# AI_Camera_V1_0.net
KiCad netlist of a schematic drawn in EAGLE
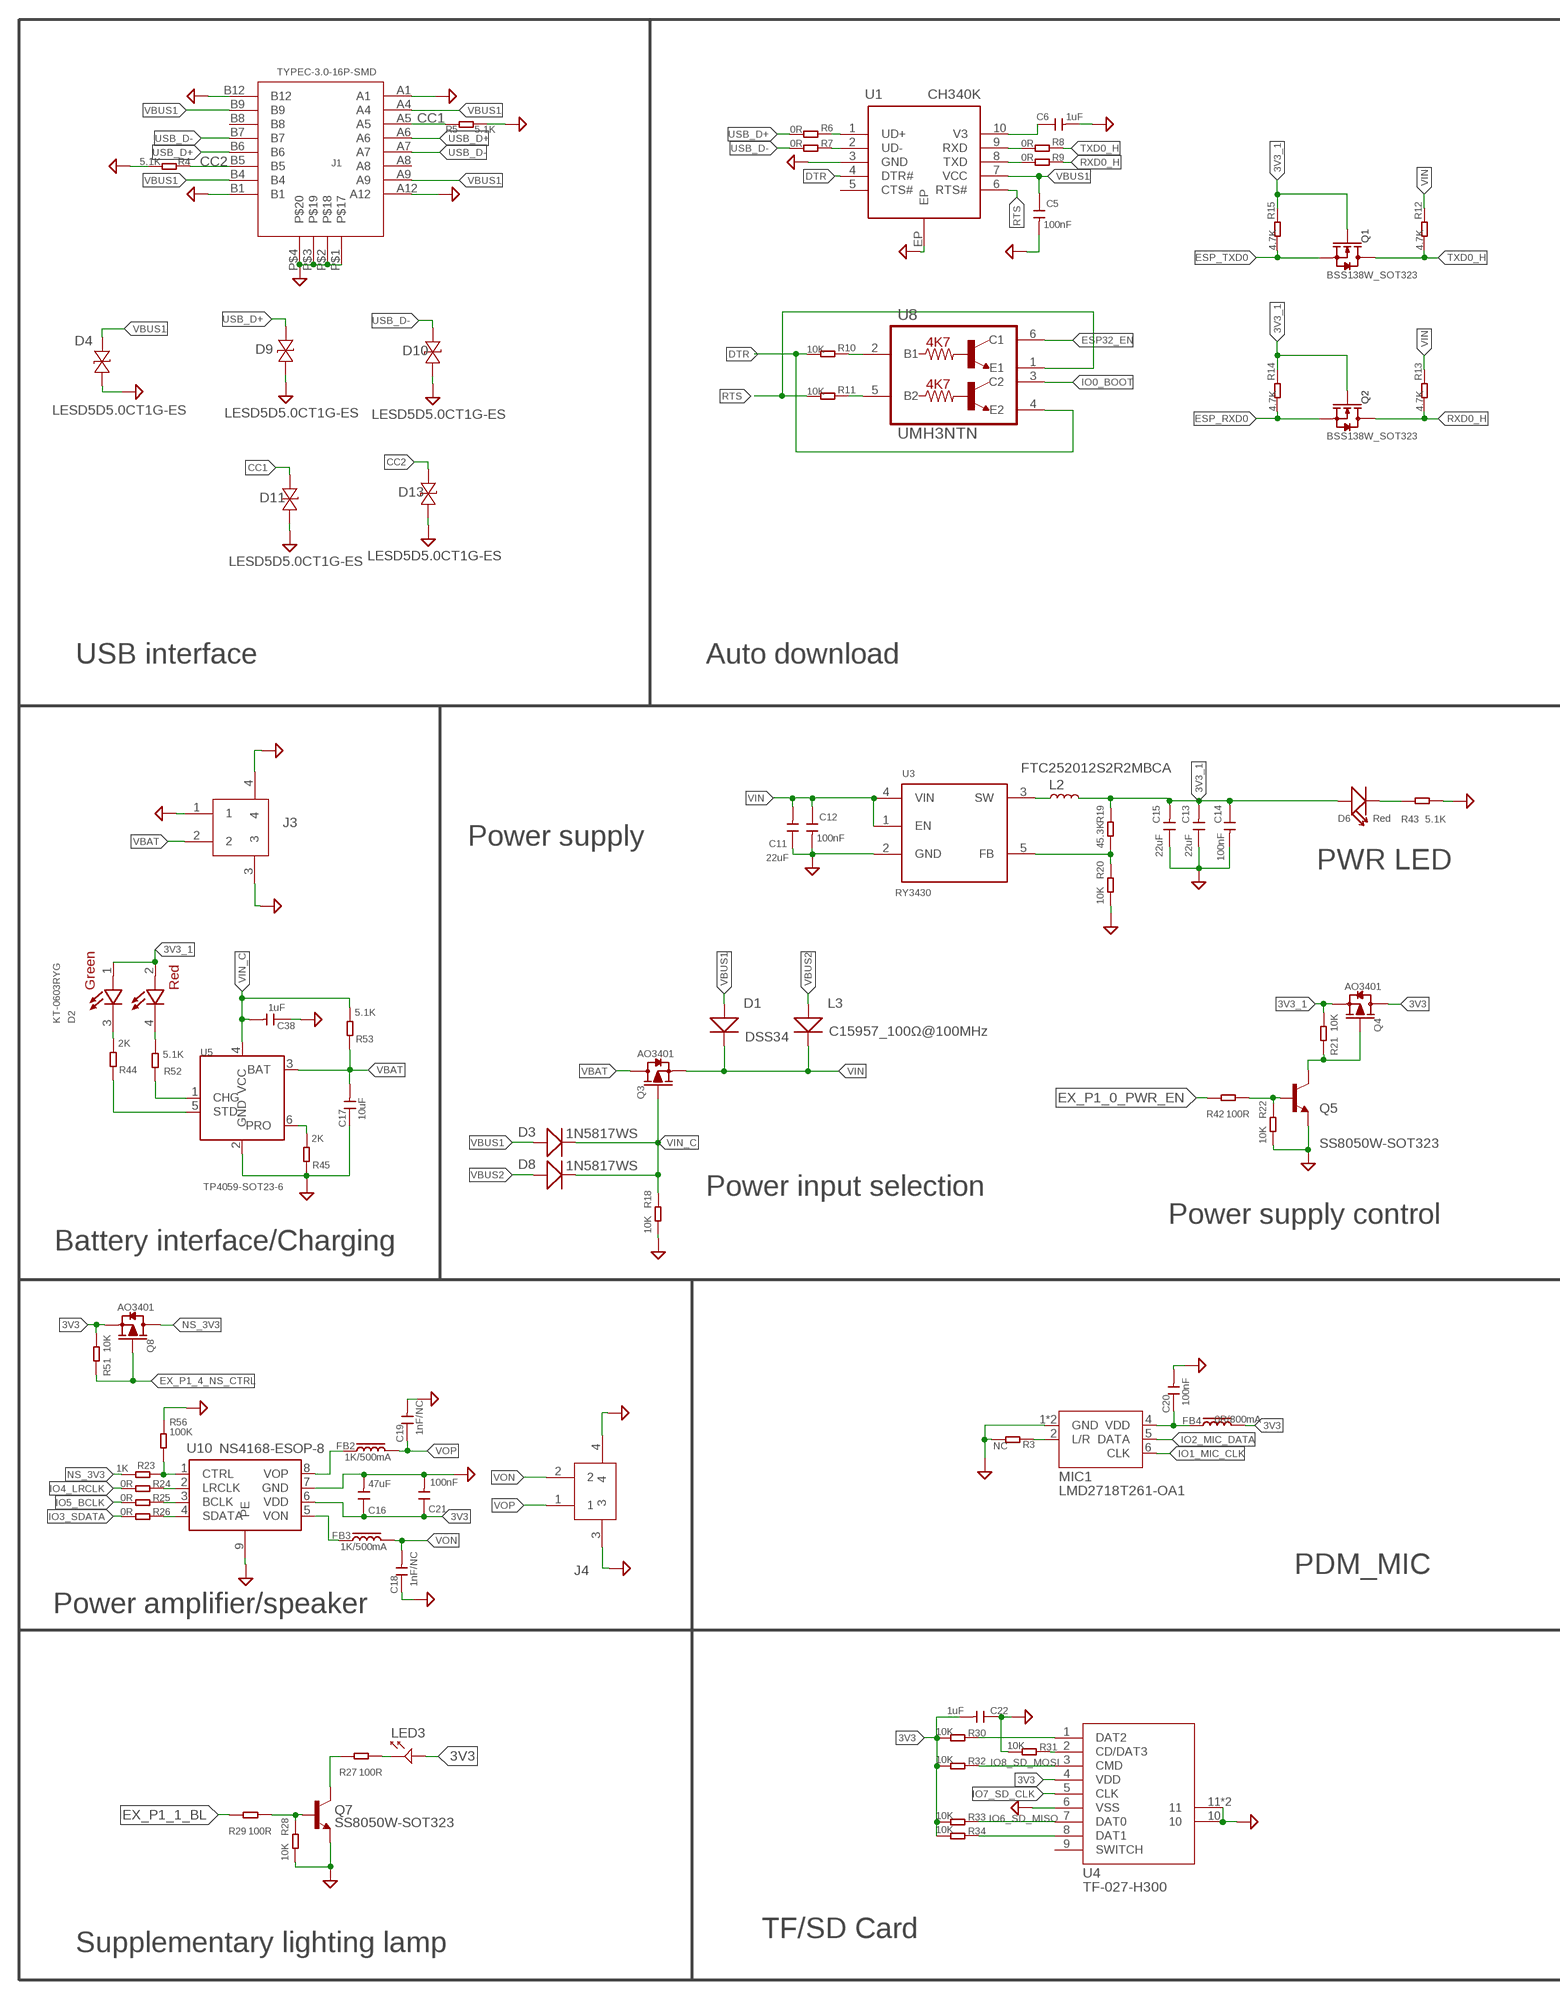
[diagram p0: schematic, sheet 1, part 1 of 2]
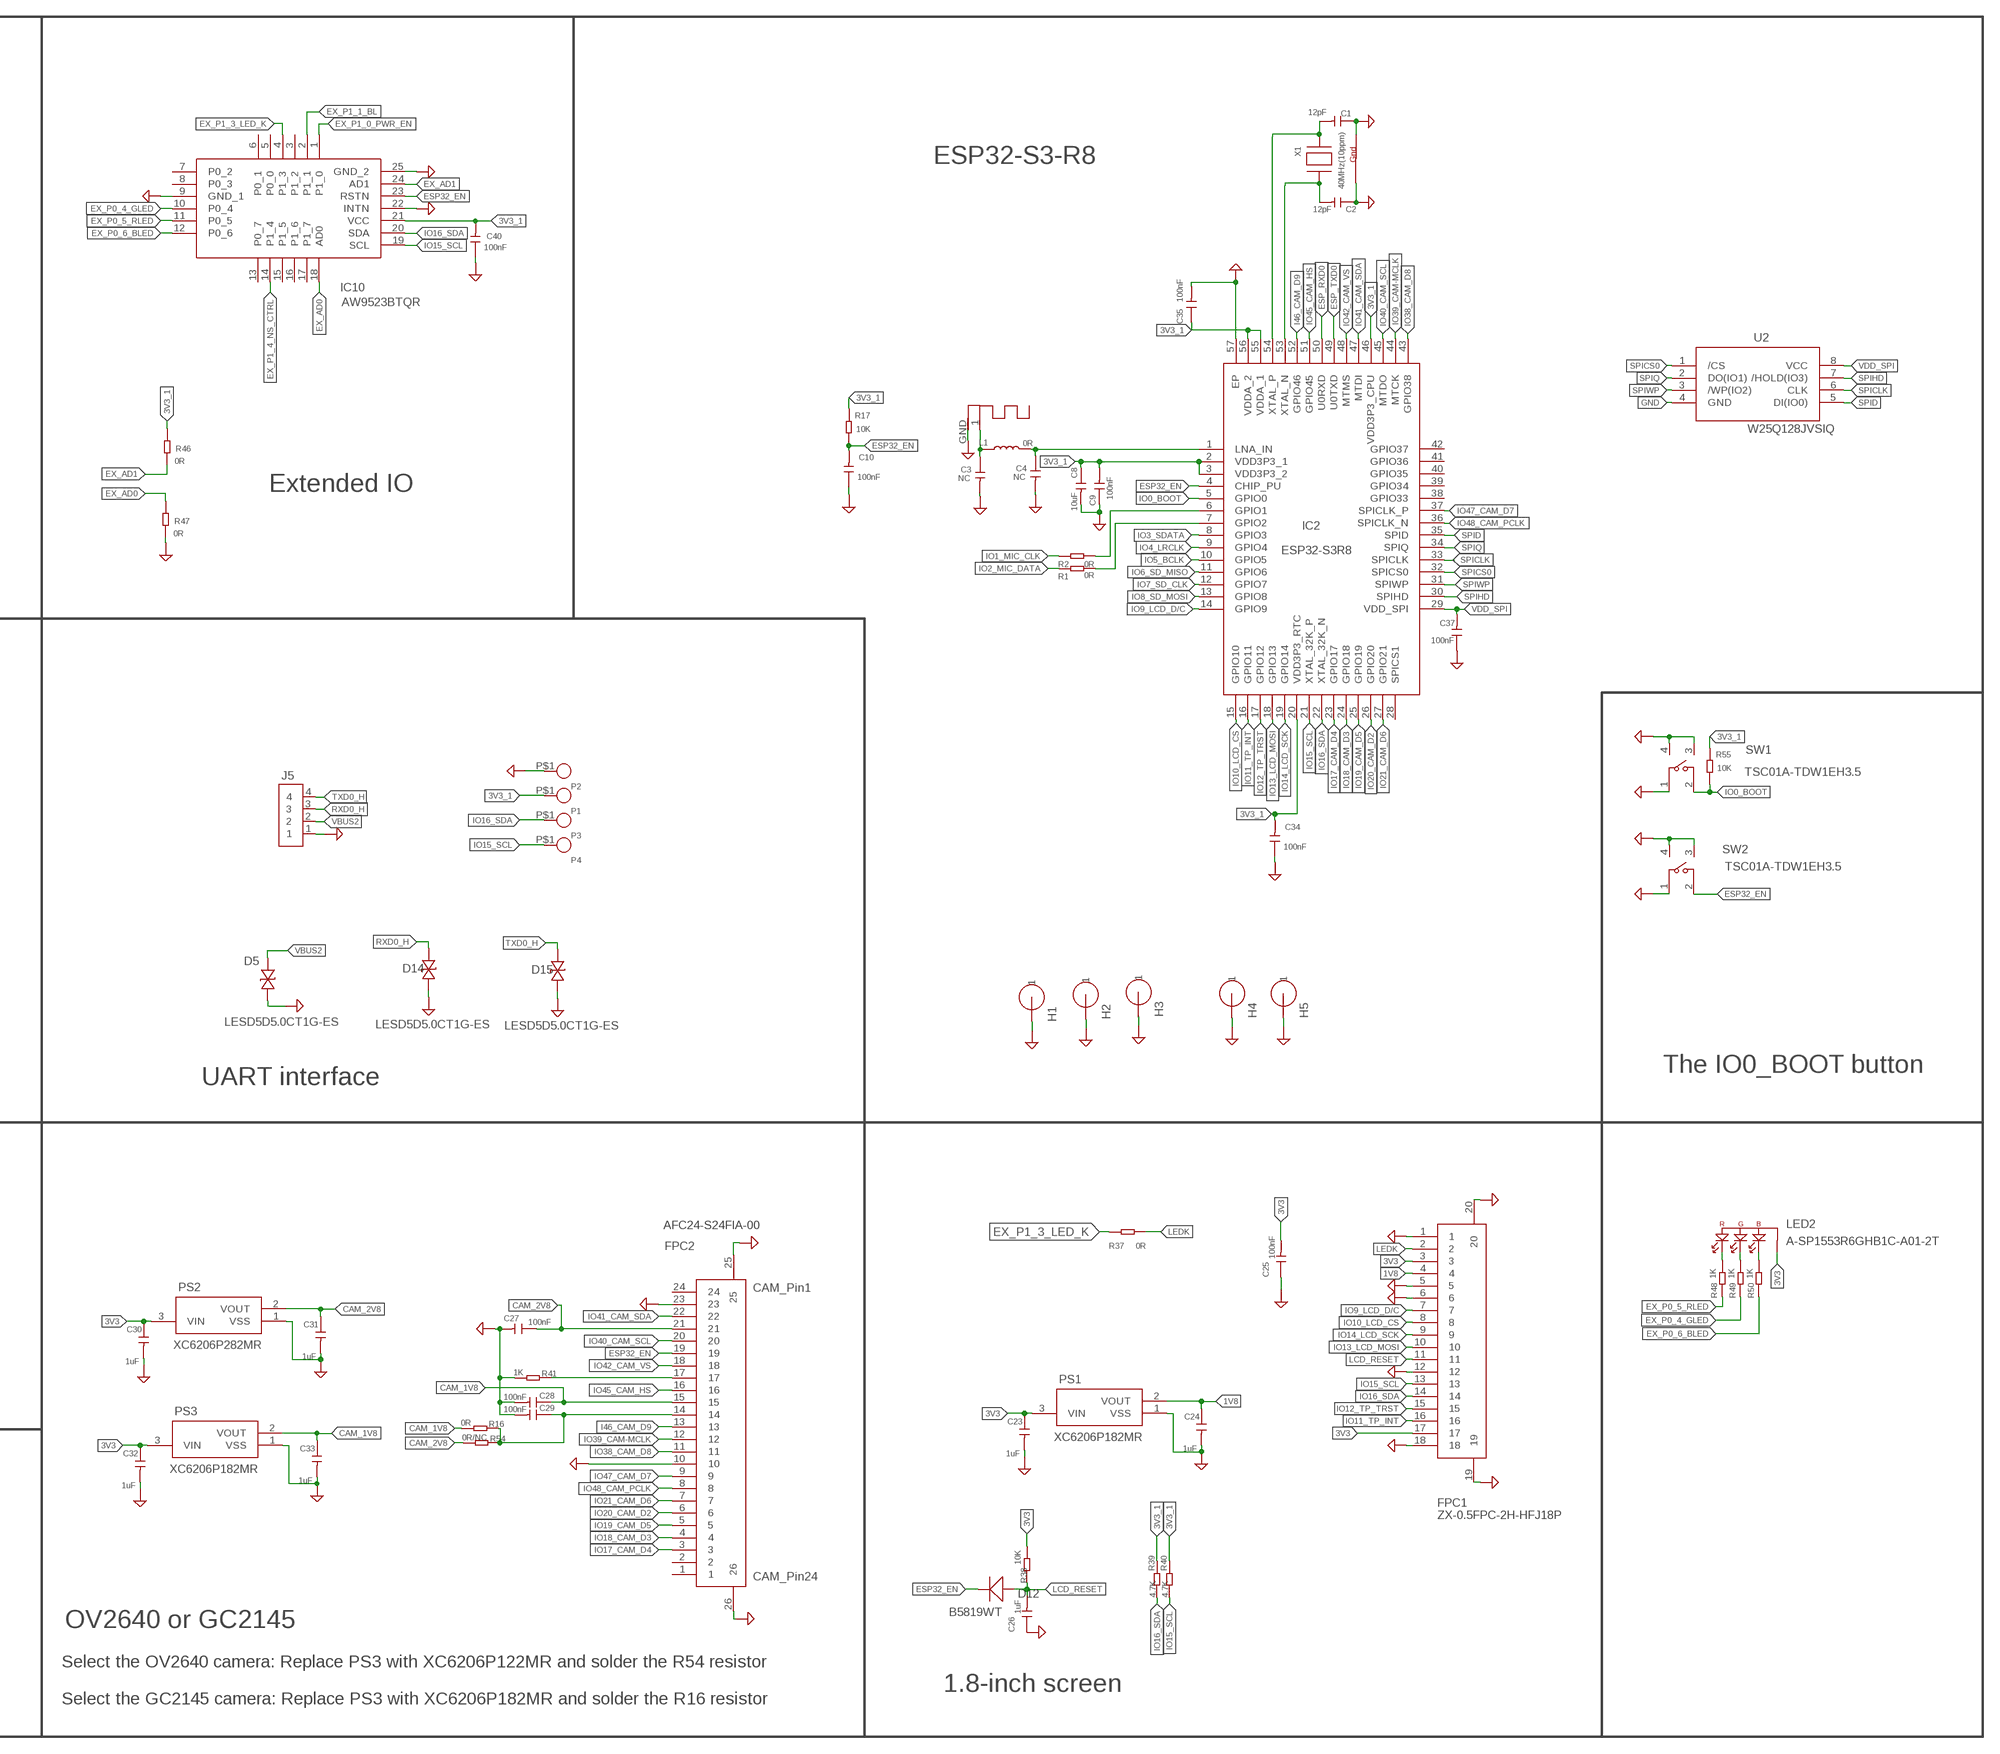
[diagram p1: schematic, sheet 1, part 2 of 2]

(export (version "E")
  (design (tool "Eeschema 10.0.6"))
  (components
    (comp (ref "ANT1")
      (value "ADAFRUIT_ANTENNA")
      (footprint "eagle-import:ADAFRUIT_RN-ANT")
      (libsource (lib "eagle-import") (part "ADAFRUIT_ANTENNA"))
    )
    (comp (ref "C1")
      (value "12pF")
      (footprint "eagle-import:C0402")
      (libsource (lib "eagle-import") (part "CAPC0402-1"))
    )
    (comp (ref "C2")
      (value "12pF")
      (footprint "eagle-import:C0402")
      (libsource (lib "eagle-import") (part "CAPC0402-1"))
    )
    (comp (ref "C3")
      (value "NC")
      (footprint "eagle-import:C0402")
      (libsource (lib "eagle-import") (part "CAPC0402-1"))
    )
    (comp (ref "C4")
      (value "NC")
      (footprint "eagle-import:C0402")
      (libsource (lib "eagle-import") (part "CAPC0402-1"))
    )
    (comp (ref "C5")
      (value "100nF")
      (footprint "eagle-import:C0402")
      (libsource (lib "eagle-import") (part "CAPC0402-1"))
    )
    (comp (ref "C6")
      (value "1uF")
      (footprint "eagle-import:C0402")
      (libsource (lib "eagle-import") (part "CAPC0402-1"))
    )
    (comp (ref "C8")
      (value "10uF")
      (footprint "eagle-import:C0402")
      (libsource (lib "eagle-import") (part "CAPC0402-1"))
    )
    (comp (ref "C9")
      (value "100nF")
      (footprint "eagle-import:C0402")
      (libsource (lib "eagle-import") (part "CAPC0402-1"))
    )
    (comp (ref "C10")
      (value "100nF")
      (footprint "eagle-import:C0402")
      (libsource (lib "eagle-import") (part "CAPC0402-1"))
    )
    (comp (ref "C11")
      (value "22uF")
      (footprint "eagle-import:C0603")
      (libsource (lib "eagle-import") (part "CAP"))
    )
    (comp (ref "C12")
      (value "100nF")
      (footprint "eagle-import:C0402")
      (libsource (lib "eagle-import") (part "CAPC0402-1"))
    )
    (comp (ref "C13")
      (value "22uF")
      (footprint "eagle-import:C0603")
      (libsource (lib "eagle-import") (part "CAP"))
    )
    (comp (ref "C14")
      (value "100nF")
      (footprint "eagle-import:C0402")
      (libsource (lib "eagle-import") (part "CAPC0402-1"))
    )
    (comp (ref "C15")
      (value "22uF")
      (footprint "eagle-import:C0603")
      (libsource (lib "eagle-import") (part "CAP"))
    )
    (comp (ref "C16")
      (value "47uF")
      (footprint "eagle-import:C0805")
      (libsource (lib "eagle-import") (part "CAPC0805"))
    )
    (comp (ref "C17")
      (value "10uF")
      (footprint "eagle-import:C0402")
      (libsource (lib "eagle-import") (part "CAPC0402-1"))
    )
    (comp (ref "C18")
      (value "1nF/NC")
      (footprint "eagle-import:C0402")
      (libsource (lib "eagle-import") (part "CAPC0402-1"))
    )
    (comp (ref "C19")
      (value "1nF/NC")
      (footprint "eagle-import:C0402")
      (libsource (lib "eagle-import") (part "CAPC0402-1"))
    )
    (comp (ref "C20")
      (value "100nF")
      (footprint "eagle-import:C0402")
      (libsource (lib "eagle-import") (part "CAPC0402-1"))
    )
    (comp (ref "C21")
      (value "100nF")
      (footprint "eagle-import:C0402")
      (libsource (lib "eagle-import") (part "CAPC0402-1"))
    )
    (comp (ref "C22")
      (value "1uF")
      (footprint "eagle-import:C0402")
      (libsource (lib "eagle-import") (part "CAPC0402-1"))
    )
    (comp (ref "C23")
      (value "1uF")
      (footprint "eagle-import:C0402")
      (libsource (lib "eagle-import") (part "CAPC0402-1"))
    )
    (comp (ref "C24")
      (value "1uF")
      (footprint "eagle-import:C0402")
      (libsource (lib "eagle-import") (part "CAPC0402-1"))
    )
    (comp (ref "C25")
      (value "100nF")
      (footprint "eagle-import:C0402")
      (libsource (lib "eagle-import") (part "CAPC0402-1"))
    )
    (comp (ref "C26")
      (value "1uF")
      (footprint "eagle-import:C0402")
      (libsource (lib "eagle-import") (part "CAPC0402-1"))
    )
    (comp (ref "C27")
      (value "100nF")
      (footprint "eagle-import:C0402")
      (libsource (lib "eagle-import") (part "CAPC0402-1"))
    )
    (comp (ref "C28")
      (value "100nF")
      (footprint "eagle-import:C0402")
      (libsource (lib "eagle-import") (part "CAPC0402-1"))
    )
    (comp (ref "C29")
      (value "100nF")
      (footprint "eagle-import:C0402")
      (libsource (lib "eagle-import") (part "CAPC0402-1"))
    )
    (comp (ref "C30")
      (value "1uF")
      (footprint "eagle-import:C0402")
      (libsource (lib "eagle-import") (part "CAPC0402-1"))
    )
    (comp (ref "C31")
      (value "1uF")
      (footprint "eagle-import:C0402")
      (libsource (lib "eagle-import") (part "CAPC0402-1"))
    )
    (comp (ref "C32")
      (value "1uF")
      (footprint "eagle-import:C0402")
      (libsource (lib "eagle-import") (part "CAPC0402-1"))
    )
    (comp (ref "C33")
      (value "1uF")
      (footprint "eagle-import:C0402")
      (libsource (lib "eagle-import") (part "CAPC0402-1"))
    )
    (comp (ref "C34")
      (value "100nF")
      (footprint "eagle-import:C0402")
      (libsource (lib "eagle-import") (part "CAPC0402-1"))
    )
    (comp (ref "C35")
      (value "100nF")
      (footprint "eagle-import:C0402")
      (libsource (lib "eagle-import") (part "CAPC0402-1"))
    )
    (comp (ref "C37")
      (value "100nF")
      (footprint "eagle-import:C0402")
      (libsource (lib "eagle-import") (part "CAPC0402-1"))
    )
    (comp (ref "C38")
      (value "1uF")
      (footprint "eagle-import:C0402")
      (libsource (lib "eagle-import") (part "CAPC0402-1"))
    )
    (comp (ref "C40")
      (value "100nF")
      (footprint "eagle-import:C0402")
      (libsource (lib "eagle-import") (part "CAPC0402-1"))
    )
    (comp (ref "D1")
      (value "DSS34")
      (footprint "eagle-import:D_SOD123FL")
      (libsource (lib "eagle-import") (part "DIODE"))
    )
    (comp (ref "D2")
      (value "KT-0603RYG")
      (footprint "eagle-import:LED_KT-0603RYG")
      (libsource (lib "eagle-import") (part "KT-0603RYG"))
    )
    (comp (ref "D3")
      (value "1N5817WS")
      (footprint "eagle-import:D_SOD323")
      (libsource (lib "eagle-import") (part "DIODE0805"))
    )
    (comp (ref "D4")
      (value "LESD5D5.0CT1G-ES")
      (footprint "eagle-import:SOD-523_L1.2-W0.8-LS1.6-BI")
      (libsource (lib "eagle-import") (part "LESD5D5.0CT1G-ES"))
    )
    (comp (ref "D5")
      (value "LESD5D5.0CT1G-ES")
      (footprint "eagle-import:SOD-523_L1.2-W0.8-LS1.6-BI")
      (libsource (lib "eagle-import") (part "LESD5D5.0CT1G-ES"))
    )
    (comp (ref "D6")
      (value "Red")
      (footprint "eagle-import:LED0603")
      (libsource (lib "eagle-import") (part "LED-SMT0603"))
    )
    (comp (ref "D8")
      (value "1N5817WS")
      (footprint "eagle-import:D_SOD323")
      (libsource (lib "eagle-import") (part "DIODE0805"))
    )
    (comp (ref "D9")
      (value "LESD5D5.0CT1G-ES")
      (footprint "eagle-import:SOD-523_L1.2-W0.8-LS1.6-BI")
      (libsource (lib "eagle-import") (part "LESD5D5.0CT1G-ES"))
    )
    (comp (ref "D10")
      (value "LESD5D5.0CT1G-ES")
      (footprint "eagle-import:SOD-523_L1.2-W0.8-LS1.6-BI")
      (libsource (lib "eagle-import") (part "LESD5D5.0CT1G-ES"))
    )
    (comp (ref "D11")
      (value "LESD5D5.0CT1G-ES")
      (footprint "eagle-import:SOD-523_L1.2-W0.8-LS1.6-BI")
      (libsource (lib "eagle-import") (part "LESD5D5.0CT1G-ES"))
    )
    (comp (ref "D12")
      (value "B5819WT")
      (footprint "eagle-import:D_SOD523")
      (libsource (lib "eagle-import") (part "DIODE0603"))
    )
    (comp (ref "D13")
      (value "LESD5D5.0CT1G-ES")
      (footprint "eagle-import:SOD-523_L1.2-W0.8-LS1.6-BI")
      (libsource (lib "eagle-import") (part "LESD5D5.0CT1G-ES"))
    )
    (comp (ref "D14")
      (value "LESD5D5.0CT1G-ES")
      (footprint "eagle-import:SOD-523_L1.2-W0.8-LS1.6-BI")
      (libsource (lib "eagle-import") (part "LESD5D5.0CT1G-ES"))
    )
    (comp (ref "D15")
      (value "LESD5D5.0CT1G-ES")
      (footprint "eagle-import:SOD-523_L1.2-W0.8-LS1.6-BI")
      (libsource (lib "eagle-import") (part "LESD5D5.0CT1G-ES"))
    )
    (comp (ref "FB2")
      (value "1K/500mA")
      (footprint "eagle-import:L0603")
      (libsource (lib "eagle-import") (part "FBL0603"))
    )
    (comp (ref "FB3")
      (value "1K/500mA")
      (footprint "eagle-import:L0603")
      (libsource (lib "eagle-import") (part "FBL0603"))
    )
    (comp (ref "FB4")
      (value "0R/800mA")
      (footprint "eagle-import:L0603")
      (libsource (lib "eagle-import") (part "FBL0603"))
    )
    (comp (ref "FPC1")
      (value "ZX-0.5FPC-2H-HFJ18P")
      (footprint "eagle-import:FPC-SMD_18P-P0.50_ZX-0.5FPC-2H-HFJ18P")
      (libsource (lib "eagle-import") (part "ZX-0.5FPC-2H-HFJ18P"))
    )
    (comp (ref "FPC2")
      (value "AFC24-S24FIA-00")
      (footprint "eagle-import:FPC-SMD_P0.50-24P_QCHF-SM-H2.0")
      (libsource (lib "eagle-import") (part "AFC24-S24FIA-00"))
    )
    (comp (ref "H1")
      (value "HOLE")
      (footprint "eagle-import:HOLE_M2")
      (libsource (lib "eagle-import") (part "HOLE"))
    )
    (comp (ref "H2")
      (value "HOLE")
      (footprint "eagle-import:HOLE_M2")
      (libsource (lib "eagle-import") (part "HOLE"))
    )
    (comp (ref "H3")
      (value "HOLE")
      (footprint "eagle-import:HOLE_M2")
      (libsource (lib "eagle-import") (part "HOLE"))
    )
    (comp (ref "H4")
      (value "HOLE1")
      (footprint "eagle-import:LONGSTRIPHOLE")
      (libsource (lib "eagle-import") (part "HOLE1"))
    )
    (comp (ref "H5")
      (value "HOLE1")
      (footprint "eagle-import:LONGSTRIPHOLE")
      (libsource (lib "eagle-import") (part "HOLE1"))
    )
    (comp (ref "IC2")
      (value "ESP32-S3R8")
      (footprint "eagle-import:QFN40P700X700X90-57N")
      (fields (field (name "MOUSER_PART_NUMBER") "356-ESP32-S3R8"))
      (libsource (lib "eagle-import") (part "ESP32-S3R8"))
    )
    (comp (ref "IC10")
      (value "AW9523BTQR")
      (footprint "eagle-import:QFN50P400X400X80-25N")
      (libsource (lib "eagle-import") (part "AW9523BTQR"))
    )
    (comp (ref "J1")
      (value "TYPEC-3.0-16P-SMD")
      (footprint "eagle-import:USB-3.0TYPEC-SMD")
      (libsource (lib "eagle-import") (part "TYPEC-3.0-16P-SMD"))
    )
    (comp (ref "J3")
      (value "ZX-SH1.0-2PLT1")
      (footprint "eagle-import:CONN-SMD_2P-P1.00_XUNPU_WAFER-SH1.0-2PWB")
      (libsource (lib "eagle-import") (part "ZX-SH1.0-2PLT1"))
    )
    (comp (ref "J4")
      (value "HC-1.25-2PWT")
      (footprint "eagle-import:CONN-SMD_2P-P1.25-HC-1.25-2PWT")
      (libsource (lib "eagle-import") (part "HC-1.25-2PWT"))
    )
    (comp (ref "J5")
      (value "HC-HY-4A-M")
      (footprint "eagle-import:CONN-TH_4P-P2.00_HCTL_HC-HY-4A")
      (libsource (lib "eagle-import") (part "HC-HY-4A-M"))
    )
    (comp (ref "L1")
      (value "0R")
      (footprint "eagle-import:L0402")
      (libsource (lib "eagle-import") (part "L0402"))
    )
    (comp (ref "L2")
      (value "FTC252012S2R2MBCA")
      (footprint "eagle-import:IND-SMD_L2.5-W2.0_MHCHL2520")
      (libsource (lib "eagle-import") (part "FTC252012S2R2MBCA"))
    )
    (comp (ref "L3")
      (value "C15957_100Ω@100MHz")
      (footprint "eagle-import:D_SOD123FL")
      (libsource (lib "eagle-import") (part "DIODE"))
    )
    (comp (ref "LED2")
      (value "A-SP1553R6GHB1C-A01-2T")
      (footprint "eagle-import:LED-SMD_4P-L3.2-W2.7-BL_A-SP1553R6GHB1C-A01-2T")
      (libsource (lib "eagle-import") (part "A-SP1553R6GHB1C-A01-2T"))
    )
    (comp (ref "LED3")
      (value "3014_LED")
      (footprint "eagle-import:LED_3014_SMT")
      (libsource (lib "eagle-import") (part "3014_LED"))
    )
    (comp (ref "MIC1")
      (value "LMD2718T261-OA1")
      (footprint "eagle-import:MIC-SMD_6P-L2.8-W1.9-P0.98-TL")
      (libsource (lib "eagle-import") (part "LMD2718T261-OA1"))
    )
    (comp (ref "P1")
      (value "TEST_PADPAD-1.5MM")
      (footprint "eagle-import:TEST_PAD-1.5MM")
      (libsource (lib "eagle-import") (part "TEST_PADPAD-1.5MM"))
    )
    (comp (ref "P2")
      (value "TEST_PADPAD-1.5MM")
      (footprint "eagle-import:TEST_PAD-1.5MM")
      (libsource (lib "eagle-import") (part "TEST_PADPAD-1.5MM"))
    )
    (comp (ref "P3")
      (value "TEST_PADPAD-1.5MM")
      (footprint "eagle-import:TEST_PAD-1.5MM")
      (libsource (lib "eagle-import") (part "TEST_PADPAD-1.5MM"))
    )
    (comp (ref "P4")
      (value "TEST_PADPAD-1.5MM")
      (footprint "eagle-import:TEST_PAD-1.5MM")
      (libsource (lib "eagle-import") (part "TEST_PADPAD-1.5MM"))
    )
    (comp (ref "PS1")
      (value "XC6206P182MR")
      (footprint "eagle-import:SOT95P280X130-3N")
      (libsource (lib "eagle-import") (part "XC6206P182MR"))
    )
    (comp (ref "PS2")
      (value "XC6206P282MR")
      (footprint "eagle-import:SOT95P280X130-3N")
      (fields (field (name "MANUFACTURER_PART_NUMBER") "XC6206P182MR"))
      (libsource (lib "eagle-import") (part "XC6206P182MR"))
    )
    (comp (ref "PS3")
      (value "XC6206P182MR")
      (footprint "eagle-import:SOT95P280X130-3N")
      (libsource (lib "eagle-import") (part "XC6206P182MR"))
    )
    (comp (ref "Q1")
      (value "BSS138W_SOT323")
      (footprint "eagle-import:MOS_SOT323")
      (libsource (lib "eagle-import") (part "MOSFET-NSI1304BDL"))
    )
    (comp (ref "Q2")
      (value "BSS138W_SOT323")
      (footprint "eagle-import:MOS_SOT323")
      (libsource (lib "eagle-import") (part "MOSFET-NSI1304BDL"))
    )
    (comp (ref "Q3")
      (value "AO3401")
      (footprint "eagle-import:PMOS_SOT23")
      (libsource (lib "eagle-import") (part "MOSFET-PSOT23"))
    )
    (comp (ref "Q4")
      (value "AO3401")
      (footprint "eagle-import:PMOS_SOT23")
      (libsource (lib "eagle-import") (part "MOSFET-PSOT23"))
    )
    (comp (ref "Q5")
      (value "SS8050W-SOT323")
      (footprint "eagle-import:MOS_SOT323")
      (libsource (lib "eagle-import") (part "TRANS_NPN"))
    )
    (comp (ref "Q7")
      (value "SS8050W-SOT323")
      (footprint "eagle-import:MOS_SOT323")
      (libsource (lib "eagle-import") (part "TRANS_NPN"))
    )
    (comp (ref "Q8")
      (value "AO3401")
      (footprint "eagle-import:PMOS_SOT23")
      (libsource (lib "eagle-import") (part "MOSFET-PSOT23"))
    )
    (comp (ref "R1")
      (value "0R")
      (footprint "eagle-import:R0402")
      (libsource (lib "eagle-import") (part "RES-0402"))
    )
    (comp (ref "R2")
      (value "0R")
      (footprint "eagle-import:R0402")
      (libsource (lib "eagle-import") (part "RES-0402"))
    )
    (comp (ref "R3")
      (value "NC")
      (footprint "eagle-import:R0402")
      (libsource (lib "eagle-import") (part "RES-0402"))
    )
    (comp (ref "R4")
      (value "5.1K")
      (footprint "eagle-import:R0402")
      (libsource (lib "eagle-import") (part "RES-0402"))
    )
    (comp (ref "R5")
      (value "5.1K")
      (footprint "eagle-import:R0402")
      (libsource (lib "eagle-import") (part "RES-0402"))
    )
    (comp (ref "R6")
      (value "0R")
      (footprint "eagle-import:R0402")
      (libsource (lib "eagle-import") (part "RES-0402"))
    )
    (comp (ref "R7")
      (value "0R")
      (footprint "eagle-import:R0402")
      (libsource (lib "eagle-import") (part "RES-0402"))
    )
    (comp (ref "R8")
      (value "0R")
      (footprint "eagle-import:R0402")
      (libsource (lib "eagle-import") (part "RES-0402"))
    )
    (comp (ref "R9")
      (value "0R")
      (footprint "eagle-import:R0402")
      (libsource (lib "eagle-import") (part "RES-0402"))
    )
    (comp (ref "R10")
      (value "10K")
      (footprint "eagle-import:R0402")
      (libsource (lib "eagle-import") (part "RES-0402"))
    )
    (comp (ref "R11")
      (value "10K")
      (footprint "eagle-import:R0402")
      (libsource (lib "eagle-import") (part "RES-0402"))
    )
    (comp (ref "R12")
      (value "4.7K")
      (footprint "eagle-import:R0402")
      (libsource (lib "eagle-import") (part "RES-0402"))
    )
    (comp (ref "R13")
      (value "4.7K")
      (footprint "eagle-import:R0402")
      (libsource (lib "eagle-import") (part "RES-0402"))
    )
    (comp (ref "R14")
      (value "4.7K")
      (footprint "eagle-import:R0402")
      (libsource (lib "eagle-import") (part "RES-0402"))
    )
    (comp (ref "R15")
      (value "4.7K")
      (footprint "eagle-import:R0402")
      (libsource (lib "eagle-import") (part "RES-0402"))
    )
    (comp (ref "R16")
      (value "0R")
      (footprint "eagle-import:R0402")
      (libsource (lib "eagle-import") (part "RES-0402"))
    )
    (comp (ref "R17")
      (value "10K")
      (footprint "eagle-import:R0402")
      (libsource (lib "eagle-import") (part "RES-0402"))
    )
    (comp (ref "R18")
      (value "10K")
      (footprint "eagle-import:R0402")
      (libsource (lib "eagle-import") (part "RES-0402"))
    )
    (comp (ref "R19")
      (value "45.3K")
      (footprint "eagle-import:R0402")
      (libsource (lib "eagle-import") (part "RES-0402"))
    )
    (comp (ref "R20")
      (value "10K")
      (footprint "eagle-import:R0402")
      (libsource (lib "eagle-import") (part "RES-0402"))
    )
    (comp (ref "R21")
      (value "10K")
      (footprint "eagle-import:R0402")
      (libsource (lib "eagle-import") (part "RES-0402"))
    )
    (comp (ref "R22")
      (value "10K")
      (footprint "eagle-import:R0402")
      (libsource (lib "eagle-import") (part "RES-0402"))
    )
    (comp (ref "R23")
      (value "1K")
      (footprint "eagle-import:R0402")
      (libsource (lib "eagle-import") (part "RES-0402"))
    )
    (comp (ref "R24")
      (value "0R")
      (footprint "eagle-import:R0402")
      (libsource (lib "eagle-import") (part "RES-0402"))
    )
    (comp (ref "R25")
      (value "0R")
      (footprint "eagle-import:R0402")
      (libsource (lib "eagle-import") (part "RES-0402"))
    )
    (comp (ref "R26")
      (value "0R")
      (footprint "eagle-import:R0402")
      (libsource (lib "eagle-import") (part "RES-0402"))
    )
    (comp (ref "R27")
      (value "100R")
      (footprint "eagle-import:R0402")
      (libsource (lib "eagle-import") (part "RES-0402"))
    )
    (comp (ref "R28")
      (value "10K")
      (footprint "eagle-import:R0402")
      (libsource (lib "eagle-import") (part "RES-0402"))
    )
    (comp (ref "R29")
      (value "100R")
      (footprint "eagle-import:R0402")
      (libsource (lib "eagle-import") (part "RES-0402"))
    )
    (comp (ref "R30")
      (value "10K")
      (footprint "eagle-import:R0402")
      (libsource (lib "eagle-import") (part "RES-0402"))
    )
    (comp (ref "R31")
      (value "10K")
      (footprint "eagle-import:R0402")
      (libsource (lib "eagle-import") (part "RES-0402"))
    )
    (comp (ref "R32")
      (value "10K")
      (footprint "eagle-import:R0402")
      (libsource (lib "eagle-import") (part "RES-0402"))
    )
    (comp (ref "R33")
      (value "10K")
      (footprint "eagle-import:R0402")
      (libsource (lib "eagle-import") (part "RES-0402"))
    )
    (comp (ref "R34")
      (value "10K")
      (footprint "eagle-import:R0402")
      (libsource (lib "eagle-import") (part "RES-0402"))
    )
    (comp (ref "R37")
      (value "0R")
      (footprint "eagle-import:R0402")
      (libsource (lib "eagle-import") (part "RES-0402"))
    )
    (comp (ref "R38")
      (value "10K")
      (footprint "eagle-import:R0402")
      (libsource (lib "eagle-import") (part "RES-0402"))
    )
    (comp (ref "R39")
      (value "4.7K")
      (footprint "eagle-import:R0402")
      (libsource (lib "eagle-import") (part "RES-0402"))
    )
    (comp (ref "R40")
      (value "4.7K")
      (footprint "eagle-import:R0402")
      (libsource (lib "eagle-import") (part "RES-0402"))
    )
    (comp (ref "R41")
      (value "1K")
      (footprint "eagle-import:R0402")
      (libsource (lib "eagle-import") (part "RES-0402"))
    )
    (comp (ref "R42")
      (value "100R")
      (footprint "eagle-import:R0402")
      (libsource (lib "eagle-import") (part "RES-0402"))
    )
    (comp (ref "R43")
      (value "5.1K")
      (footprint "eagle-import:R0402")
      (libsource (lib "eagle-import") (part "RES-0402"))
    )
    (comp (ref "R44")
      (value "2K")
      (footprint "eagle-import:R0402")
      (libsource (lib "eagle-import") (part "RES-0402"))
    )
    (comp (ref "R45")
      (value "2K")
      (footprint "eagle-import:R0402")
      (libsource (lib "eagle-import") (part "RES-0402"))
    )
    (comp (ref "R46")
      (value "0R")
      (footprint "eagle-import:R0402")
      (libsource (lib "eagle-import") (part "RES-0402"))
    )
    (comp (ref "R47")
      (value "0R")
      (footprint "eagle-import:R0402")
      (libsource (lib "eagle-import") (part "RES-0402"))
    )
    (comp (ref "R48")
      (value "1K")
      (footprint "eagle-import:R0402")
      (libsource (lib "eagle-import") (part "RES-0402"))
    )
    (comp (ref "R49")
      (value "1K")
      (footprint "eagle-import:R0402")
      (libsource (lib "eagle-import") (part "RES-0402"))
    )
    (comp (ref "R50")
      (value "1K")
      (footprint "eagle-import:R0402")
      (libsource (lib "eagle-import") (part "RES-0402"))
    )
    (comp (ref "R51")
      (value "10K")
      (footprint "eagle-import:R0402")
      (libsource (lib "eagle-import") (part "RES-0402"))
    )
    (comp (ref "R52")
      (value "5.1K")
      (footprint "eagle-import:R0402")
      (libsource (lib "eagle-import") (part "RES-0402"))
    )
    (comp (ref "R53")
      (value "5.1K")
      (footprint "eagle-import:R0402")
      (libsource (lib "eagle-import") (part "RES-0402"))
    )
    (comp (ref "R54")
      (value "0R/NC")
      (footprint "eagle-import:R0402")
      (libsource (lib "eagle-import") (part "RES-0402"))
    )
    (comp (ref "R55")
      (value "10K")
      (footprint "eagle-import:R0402")
      (libsource (lib "eagle-import") (part "RES-0402"))
    )
    (comp (ref "R56")
      (value "100K")
      (footprint "eagle-import:R0402")
      (libsource (lib "eagle-import") (part "RES-0402"))
    )
    (comp (ref "SW1")
      (value "TSC01A-TDW1EH3.5")
      (footprint "eagle-import:KEY-SMD_4P-L4.6-W2.4_TSC01A-TDW1FH3.5")
      (libsource (lib "eagle-import") (part "TSC01A-TDW1EH3.5"))
    )
    (comp (ref "SW2")
      (value "TSC01A-TDW1EH3.5")
      (footprint "eagle-import:KEY-SMD_4P-L4.6-W2.4_TSC01A-TDW1FH3.5")
      (libsource (lib "eagle-import") (part "TSC01A-TDW1EH3.5"))
    )
    (comp (ref "U1")
      (value "CH340K")
      (footprint "eagle-import:ESOP-10-EP-150MIL")
      (libsource (lib "eagle-import") (part "CH340K"))
    )
    (comp (ref "U2")
      (value "W25Q128JVSIQ")
      (footprint "eagle-import:CKP_W25QXX-SOP-8-208MIL")
      (libsource (lib "eagle-import") (part "CKP_W25QXXSOP"))
    )
    (comp (ref "U3")
      (value "RY3430")
      (footprint "eagle-import:IC_SOT23-5")
      (libsource (lib "eagle-import") (part "HM3416H"))
    )
    (comp (ref "U4")
      (value "TF-027-H300")
      (footprint "eagle-import:TF-SMD_HYCW104-TF08-375B")
      (libsource (lib "eagle-import") (part "TF-SMD_TF-123-ARP9H15"))
    )
    (comp (ref "U5")
      (value "TP4059-SOT23-6")
      (footprint "eagle-import:SOT23-6L")
      (libsource (lib "eagle-import") (part "TP4059-SOT23-6"))
    )
    (comp (ref "U8")
      (value "UMH3NTN")
      (footprint "eagle-import:SOP65P210X100-6N")
      (fields (field (name "MF") "Rohm"))
      (libsource (lib "eagle-import") (part "UMH3NTN"))
    )
    (comp (ref "U10")
      (value "NS4168-ESOP-8")
      (footprint "eagle-import:NS4168-ESOP-8")
      (libsource (lib "eagle-import") (part "NS4168-ESOP-8"))
    )
    (comp (ref "X1")
      (value "40MHz(10ppm)")
      (footprint "eagle-import:ADAFRUIT_NX3225")
      (libsource (lib "eagle-import") (part "ADAFRUIT_XTAL-4-3225"))
    )
  )
  (nets
    (net (code "1") (name "1V8") (class "Default")
      (node (ref "C24") (pin "1") (pinfunction "1_1") (pintype "passive"))
      (node (ref "FPC1") (pin "4") (pinfunction "4_4") (pintype "bidirectional"))
      (node (ref "PS1") (pin "2") (pinfunction "VOUT_2") (pintype "bidirectional"))
    )
    (net (code "2") (name "3V3") (class "Default")
      (node (ref "C16") (pin "1") (pinfunction "1_1") (pintype "passive"))
      (node (ref "C21") (pin "1") (pinfunction "1_1") (pintype "passive"))
      (node (ref "C22") (pin "2") (pinfunction "2_2") (pintype "passive"))
      (node (ref "C23") (pin "1") (pinfunction "1_1") (pintype "passive"))
      (node (ref "C25") (pin "2") (pinfunction "2_2") (pintype "passive"))
      (node (ref "C30") (pin "1") (pinfunction "1_1") (pintype "passive"))
      (node (ref "C32") (pin "1") (pinfunction "1_1") (pintype "passive"))
      (node (ref "FB4") (pin "2") (pinfunction "2_2") (pintype "passive"))
      (node (ref "FPC1") (pin "17") (pinfunction "17_17") (pintype "bidirectional"))
      (node (ref "FPC1") (pin "3") (pinfunction "3_3") (pintype "bidirectional"))
      (node (ref "LED2") (pin "3") (pinfunction "GND_3") (pintype "bidirectional"))
      (node (ref "LED3") (pin "1") (pinfunction "1_1") (pintype "bidirectional"))
      (node (ref "PS1") (pin "3") (pinfunction "VIN_3") (pintype "bidirectional"))
      (node (ref "PS2") (pin "3") (pinfunction "VIN_3") (pintype "bidirectional"))
      (node (ref "PS3") (pin "3") (pinfunction "VIN_3") (pintype "bidirectional"))
      (node (ref "Q4") (pin "3") (pinfunction "D_3") (pintype "passive"))
      (node (ref "Q8") (pin "2") (pinfunction "S_2") (pintype "passive"))
      (node (ref "R30") (pin "2") (pinfunction "2_2") (pintype "passive"))
      (node (ref "R32") (pin "2") (pinfunction "2_2") (pintype "passive"))
      (node (ref "R33") (pin "2") (pinfunction "2_2") (pintype "passive"))
      (node (ref "R34") (pin "2") (pinfunction "2_2") (pintype "passive"))
      (node (ref "R38") (pin "2") (pinfunction "2_2") (pintype "passive"))
      (node (ref "R51") (pin "2") (pinfunction "2_2") (pintype "passive"))
      (node (ref "U10") (pin "6") (pinfunction "VDD_6") (pintype "bidirectional"))
      (node (ref "U4") (pin "4") (pinfunction "VDD_4") (pintype "bidirectional"))
    )
    (net (code "3") (name "3V3_1") (class "Default")
      (node (ref "C13") (pin "2") (pinfunction "2_2") (pintype "passive"))
      (node (ref "C14") (pin "1") (pinfunction "1_1") (pintype "passive"))
      (node (ref "C15") (pin "2") (pinfunction "2_2") (pintype "passive"))
      (node (ref "C34") (pin "2") (pinfunction "2_2") (pintype "passive"))
      (node (ref "C35") (pin "1") (pinfunction "1_1") (pintype "passive"))
      (node (ref "C40") (pin "2") (pinfunction "2_2") (pintype "passive"))
      (node (ref "C8") (pin "1") (pinfunction "1_1") (pintype "passive"))
      (node (ref "C9") (pin "2") (pinfunction "2_2") (pintype "passive"))
      (node (ref "D2") (pin "1") (pinfunction "1_1") (pintype "passive"))
      (node (ref "D2") (pin "2") (pinfunction "2_2") (pintype "passive"))
      (node (ref "D6") (pin "+") (pinfunction "+_+") (pintype "passive"))
      (node (ref "IC10") (pin "21") (pinfunction "VCC_21") (pintype "bidirectional"))
      (node (ref "IC2") (pin "2") (pinfunction "VDD3P3_1_2") (pintype "bidirectional"))
      (node (ref "IC2") (pin "20") (pinfunction "VDD3P3_RTC_20") (pintype "bidirectional"))
      (node (ref "IC2") (pin "3") (pinfunction "VDD3P3_2_3") (pintype "bidirectional"))
      (node (ref "IC2") (pin "46") (pinfunction "VDD3P3_CPU_46") (pintype "bidirectional"))
      (node (ref "IC2") (pin "55") (pinfunction "VDDA_1_55") (pintype "bidirectional"))
      (node (ref "IC2") (pin "56") (pinfunction "VDDA_2_56") (pintype "bidirectional"))
      (node (ref "L2") (pin "2") (pinfunction "2_2") (pintype "bidirectional"))
      (node (ref "P1") (pin "P$1") (pinfunction "P$1_P$1") (pintype "bidirectional"))
      (node (ref "Q1") (pin "1") (pinfunction "G_1") (pintype "passive"))
      (node (ref "Q2") (pin "1") (pinfunction "G_1") (pintype "passive"))
      (node (ref "Q4") (pin "2") (pinfunction "S_2") (pintype "passive"))
      (node (ref "R14") (pin "1") (pinfunction "1_1") (pintype "passive"))
      (node (ref "R15") (pin "1") (pinfunction "1_1") (pintype "passive"))
      (node (ref "R17") (pin "1") (pinfunction "1_1") (pintype "passive"))
      (node (ref "R19") (pin "1") (pinfunction "1_1") (pintype "passive"))
      (node (ref "R21") (pin "2") (pinfunction "2_2") (pintype "passive"))
      (node (ref "R39") (pin "1") (pinfunction "1_1") (pintype "passive"))
      (node (ref "R40") (pin "1") (pinfunction "1_1") (pintype "passive"))
      (node (ref "R46") (pin "1") (pinfunction "1_1") (pintype "passive"))
      (node (ref "R55") (pin "1") (pinfunction "1_1") (pintype "passive"))
    )
    (net (code "4") (name "CAM_1V8") (class "Default")
      (node (ref "C28") (pin "1") (pinfunction "1_1") (pintype "passive"))
      (node (ref "C33") (pin "1") (pinfunction "1_1") (pintype "passive"))
      (node (ref "FPC2") (pin "15") (pinfunction "15_15") (pintype "bidirectional"))
      (node (ref "PS3") (pin "2") (pinfunction "VOUT_2") (pintype "bidirectional"))
      (node (ref "R16") (pin "2") (pinfunction "2_2") (pintype "passive"))
    )
    (net (code "5") (name "CAM_2V8") (class "Default")
      (node (ref "C27") (pin "1") (pinfunction "1_1") (pintype "passive"))
      (node (ref "C31") (pin "1") (pinfunction "1_1") (pintype "passive"))
      (node (ref "FPC2") (pin "21") (pinfunction "21_21") (pintype "bidirectional"))
      (node (ref "PS2") (pin "2") (pinfunction "VOUT_2") (pintype "bidirectional"))
      (node (ref "R54") (pin "2") (pinfunction "2_2") (pintype "passive"))
    )
    (net (code "6") (name "CC1") (class "Default")
      (node (ref "D11") (pin "2") (pinfunction "2_2") (pintype "bidirectional"))
      (node (ref "J1") (pin "A5") (pinfunction "A5_A5") (pintype "bidirectional"))
      (node (ref "R5") (pin "1") (pinfunction "1_1") (pintype "passive"))
    )
    (net (code "7") (name "CC2") (class "Default")
      (node (ref "D13") (pin "2") (pinfunction "2_2") (pintype "bidirectional"))
      (node (ref "J1") (pin "B5") (pinfunction "B5_B5") (pintype "bidirectional"))
      (node (ref "R4") (pin "1") (pinfunction "1_1") (pintype "passive"))
    )
    (net (code "8") (name "DTR") (class "Default")
      (node (ref "R10") (pin "2") (pinfunction "2_2") (pintype "passive"))
      (node (ref "U1") (pin "4") (pinfunction "DTR#_4") (pintype "bidirectional"))
      (node (ref "U8") (pin "4") (pinfunction "E2_4") (pintype "bidirectional"))
    )
    (net (code "9") (name "ESP32_EN") (class "Default")
      (node (ref "C10") (pin "2") (pinfunction "2_2") (pintype "passive"))
      (node (ref "D12") (pin "-") (pinfunction "-_-") (pintype "passive"))
      (node (ref "FPC2") (pin "19") (pinfunction "19_19") (pintype "bidirectional"))
      (node (ref "IC10") (pin "23") (pinfunction "RSTN_23") (pintype "bidirectional"))
      (node (ref "IC2") (pin "4") (pinfunction "CHIP_PU_4") (pintype "bidirectional"))
      (node (ref "R17") (pin "2") (pinfunction "2_2") (pintype "passive"))
      (node (ref "SW2") (pin "2") (pinfunction "2_2") (pintype "bidirectional"))
      (node (ref "U8") (pin "6") (pinfunction "C1_6") (pintype "bidirectional"))
    )
    (net (code "10") (name "ESP_RXD0") (class "Default")
      (node (ref "IC2") (pin "50") (pinfunction "U0RXD_50") (pintype "bidirectional"))
      (node (ref "Q2") (pin "2") (pinfunction "S_2") (pintype "passive"))
      (node (ref "R14") (pin "2") (pinfunction "2_2") (pintype "passive"))
    )
    (net (code "11") (name "ESP_TXD0") (class "Default")
      (node (ref "IC2") (pin "49") (pinfunction "U0TXD_49") (pintype "bidirectional"))
      (node (ref "Q1") (pin "2") (pinfunction "S_2") (pintype "passive"))
      (node (ref "R15") (pin "2") (pinfunction "2_2") (pintype "passive"))
    )
    (net (code "12") (name "EX_AD0") (class "Default")
      (node (ref "IC10") (pin "18") (pinfunction "AD0_18") (pintype "bidirectional"))
      (node (ref "R47") (pin "1") (pinfunction "1_1") (pintype "passive"))
    )
    (net (code "13") (name "EX_AD1") (class "Default")
      (node (ref "IC10") (pin "24") (pinfunction "AD1_24") (pintype "bidirectional"))
      (node (ref "R46") (pin "2") (pinfunction "2_2") (pintype "passive"))
    )
    (net (code "14") (name "EX_P0_4_GLED") (class "Default")
      (node (ref "IC10") (pin "10") (pinfunction "P0_4_10") (pintype "bidirectional"))
      (node (ref "R49") (pin "1") (pinfunction "1_1") (pintype "passive"))
    )
    (net (code "15") (name "EX_P0_5_RLED") (class "Default")
      (node (ref "IC10") (pin "11") (pinfunction "P0_5_11") (pintype "bidirectional"))
      (node (ref "R48") (pin "1") (pinfunction "1_1") (pintype "passive"))
    )
    (net (code "16") (name "EX_P0_6_BLED") (class "Default")
      (node (ref "IC10") (pin "12") (pinfunction "P0_6_12") (pintype "bidirectional"))
      (node (ref "R50") (pin "1") (pinfunction "1_1") (pintype "passive"))
    )
    (net (code "17") (name "EX_P1_0_PWR_EN") (class "Default")
      (node (ref "IC10") (pin "1") (pinfunction "P1_0_1") (pintype "bidirectional"))
      (node (ref "R42") (pin "1") (pinfunction "1_1") (pintype "passive"))
    )
    (net (code "18") (name "EX_P1_1_BL") (class "Default")
      (node (ref "IC10") (pin "2") (pinfunction "P1_1_2") (pintype "bidirectional"))
      (node (ref "R29") (pin "1") (pinfunction "1_1") (pintype "passive"))
    )
    (net (code "19") (name "EX_P1_3_LED_K") (class "Default")
      (node (ref "IC10") (pin "4") (pinfunction "P1_3_4") (pintype "bidirectional"))
      (node (ref "R37") (pin "1") (pinfunction "1_1") (pintype "passive"))
    )
    (net (code "20") (name "EX_P1_4_NS_CTRL") (class "Default")
      (node (ref "IC10") (pin "14") (pinfunction "P1_4_14") (pintype "bidirectional"))
      (node (ref "Q8") (pin "1") (pinfunction "G_1") (pintype "passive"))
      (node (ref "R51") (pin "1") (pinfunction "1_1") (pintype "passive"))
    )
    (net (code "21") (name "GND") (class "Default")
      (node (ref "ANT1") (pin "GND") (pinfunction "GND_GND") (pintype "passive"))
      (node (ref "C1") (pin "1") (pinfunction "1_1") (pintype "passive"))
      (node (ref "C10") (pin "1") (pinfunction "1_1") (pintype "passive"))
      (node (ref "C11") (pin "1") (pinfunction "1_1") (pintype "passive"))
      (node (ref "C12") (pin "2") (pinfunction "2_2") (pintype "passive"))
      (node (ref "C13") (pin "1") (pinfunction "1_1") (pintype "passive"))
      (node (ref "C14") (pin "2") (pinfunction "2_2") (pintype "passive"))
      (node (ref "C15") (pin "1") (pinfunction "1_1") (pintype "passive"))
      (node (ref "C16") (pin "2") (pinfunction "2_2") (pintype "passive"))
      (node (ref "C17") (pin "1") (pinfunction "1_1") (pintype "passive"))
      (node (ref "C18") (pin "1") (pinfunction "1_1") (pintype "passive"))
      (node (ref "C19") (pin "2") (pinfunction "2_2") (pintype "passive"))
      (node (ref "C2") (pin "1") (pinfunction "1_1") (pintype "passive"))
      (node (ref "C20") (pin "2") (pinfunction "2_2") (pintype "passive"))
      (node (ref "C21") (pin "2") (pinfunction "2_2") (pintype "passive"))
      (node (ref "C22") (pin "1") (pinfunction "1_1") (pintype "passive"))
      (node (ref "C23") (pin "2") (pinfunction "2_2") (pintype "passive"))
      (node (ref "C24") (pin "2") (pinfunction "2_2") (pintype "passive"))
      (node (ref "C25") (pin "1") (pinfunction "1_1") (pintype "passive"))
      (node (ref "C26") (pin "1") (pinfunction "1_1") (pintype "passive"))
      (node (ref "C27") (pin "2") (pinfunction "2_2") (pintype "passive"))
      (node (ref "C28") (pin "2") (pinfunction "2_2") (pintype "passive"))
      (node (ref "C29") (pin "2") (pinfunction "2_2") (pintype "passive"))
      (node (ref "C3") (pin "2") (pinfunction "2_2") (pintype "passive"))
      (node (ref "C30") (pin "2") (pinfunction "2_2") (pintype "passive"))
      (node (ref "C31") (pin "2") (pinfunction "2_2") (pintype "passive"))
      (node (ref "C32") (pin "2") (pinfunction "2_2") (pintype "passive"))
      (node (ref "C33") (pin "2") (pinfunction "2_2") (pintype "passive"))
      (node (ref "C34") (pin "1") (pinfunction "1_1") (pintype "passive"))
      (node (ref "C35") (pin "2") (pinfunction "2_2") (pintype "passive"))
      (node (ref "C37") (pin "1") (pinfunction "1_1") (pintype "passive"))
      (node (ref "C38") (pin "1") (pinfunction "1_1") (pintype "passive"))
      (node (ref "C4") (pin "2") (pinfunction "2_2") (pintype "passive"))
      (node (ref "C40") (pin "1") (pinfunction "1_1") (pintype "passive"))
      (node (ref "C5") (pin "2") (pinfunction "2_2") (pintype "passive"))
      (node (ref "C6") (pin "2") (pinfunction "2_2") (pintype "passive"))
      (node (ref "C8") (pin "2") (pinfunction "2_2") (pintype "passive"))
      (node (ref "C9") (pin "1") (pinfunction "1_1") (pintype "passive"))
      (node (ref "D10") (pin "1") (pinfunction "1_1") (pintype "bidirectional"))
      (node (ref "D11") (pin "1") (pinfunction "1_1") (pintype "bidirectional"))
      (node (ref "D13") (pin "1") (pinfunction "1_1") (pintype "bidirectional"))
      (node (ref "D14") (pin "1") (pinfunction "1_1") (pintype "bidirectional"))
      (node (ref "D15") (pin "1") (pinfunction "1_1") (pintype "bidirectional"))
      (node (ref "D4") (pin "1") (pinfunction "1_1") (pintype "bidirectional"))
      (node (ref "D5") (pin "1") (pinfunction "1_1") (pintype "bidirectional"))
      (node (ref "D9") (pin "1") (pinfunction "1_1") (pintype "bidirectional"))
      (node (ref "FPC1") (pin "1") (pinfunction "1_1") (pintype "bidirectional"))
      (node (ref "FPC1") (pin "12") (pinfunction "12_12") (pintype "bidirectional"))
      (node (ref "FPC1") (pin "18") (pinfunction "18_18") (pintype "bidirectional"))
      (node (ref "FPC1") (pin "19") (pinfunction "19_19") (pintype "bidirectional"))
      (node (ref "FPC1") (pin "20") (pinfunction "20_20") (pintype "bidirectional"))
      (node (ref "FPC1") (pin "5") (pinfunction "5_5") (pintype "bidirectional"))
      (node (ref "FPC1") (pin "6") (pinfunction "6_6") (pintype "bidirectional"))
      (node (ref "FPC2") (pin "10") (pinfunction "10_10") (pintype "bidirectional"))
      (node (ref "FPC2") (pin "23") (pinfunction "23_23") (pintype "bidirectional"))
      (node (ref "FPC2") (pin "25") (pinfunction "25_25") (pintype "bidirectional"))
      (node (ref "FPC2") (pin "26") (pinfunction "26_26") (pintype "bidirectional"))
      (node (ref "H1") (pin "1") (pinfunction "1_1") (pintype "bidirectional"))
      (node (ref "H2") (pin "1") (pinfunction "1_1") (pintype "bidirectional"))
      (node (ref "H3") (pin "1") (pinfunction "1_1") (pintype "bidirectional"))
      (node (ref "H4") (pin "1") (pinfunction "1_1") (pintype "bidirectional"))
      (node (ref "H4") (pin "2") (pinfunction "1_2") (pintype "bidirectional"))
      (node (ref "H5") (pin "1") (pinfunction "1_1") (pintype "bidirectional"))
      (node (ref "H5") (pin "2") (pinfunction "1_2") (pintype "bidirectional"))
      (node (ref "IC10") (pin "22") (pinfunction "INTN_22") (pintype "bidirectional"))
      (node (ref "IC10") (pin "25") (pinfunction "GND_2_25") (pintype "bidirectional"))
      (node (ref "IC10") (pin "9") (pinfunction "GND_1_9") (pintype "bidirectional"))
      (node (ref "IC2") (pin "57") (pinfunction "EP_57") (pintype "bidirectional"))
      (node (ref "J1") (pin "A1") (pinfunction "A1_A1") (pintype "bidirectional"))
      (node (ref "J1") (pin "A12") (pinfunction "A12_A12") (pintype "bidirectional"))
      (node (ref "J1") (pin "B1") (pinfunction "B1_B1") (pintype "bidirectional"))
      (node (ref "J1") (pin "B12") (pinfunction "B12_B12") (pintype "bidirectional"))
      (node (ref "J1") (pin "P$1") (pinfunction "P$17_P$1") (pintype "bidirectional"))
      (node (ref "J1") (pin "P$2") (pinfunction "P$18_P$2") (pintype "bidirectional"))
      (node (ref "J1") (pin "P$3") (pinfunction "P$19_P$3") (pintype "bidirectional"))
      (node (ref "J1") (pin "P$4") (pinfunction "P$20_P$4") (pintype "bidirectional"))
      (node (ref "J3") (pin "1") (pinfunction "1_1") (pintype "bidirectional"))
      (node (ref "J3") (pin "3") (pinfunction "3_3") (pintype "bidirectional"))
      (node (ref "J3") (pin "4") (pinfunction "4_4") (pintype "bidirectional"))
      (node (ref "J4") (pin "3") (pinfunction "3_3") (pintype "bidirectional"))
      (node (ref "J4") (pin "4") (pinfunction "4_4") (pintype "bidirectional"))
      (node (ref "J5") (pin "1") (pinfunction "1_1") (pintype "bidirectional"))
      (node (ref "MIC1") (pin "1") (pinfunction "GND_1") (pintype "bidirectional"))
      (node (ref "MIC1") (pin "3") (pinfunction "GND_3") (pintype "bidirectional"))
      (node (ref "P2") (pin "P$1") (pinfunction "P$1_P$1") (pintype "bidirectional"))
      (node (ref "PS1") (pin "1") (pinfunction "VSS_1") (pintype "bidirectional"))
      (node (ref "PS2") (pin "1") (pinfunction "VSS_1") (pintype "bidirectional"))
      (node (ref "PS3") (pin "1") (pinfunction "VSS_1") (pintype "bidirectional"))
      (node (ref "Q5") (pin "2") (pinfunction "E_2") (pintype "passive"))
      (node (ref "Q7") (pin "2") (pinfunction "E_2") (pintype "passive"))
      (node (ref "R18") (pin "2") (pinfunction "2_2") (pintype "passive"))
      (node (ref "R20") (pin "2") (pinfunction "2_2") (pintype "passive"))
      (node (ref "R22") (pin "2") (pinfunction "2_2") (pintype "passive"))
      (node (ref "R28") (pin "2") (pinfunction "2_2") (pintype "passive"))
      (node (ref "R3") (pin "2") (pinfunction "2_2") (pintype "passive"))
      (node (ref "R31") (pin "2") (pinfunction "2_2") (pintype "passive"))
      (node (ref "R4") (pin "2") (pinfunction "2_2") (pintype "passive"))
      (node (ref "R41") (pin "2") (pinfunction "2_2") (pintype "passive"))
      (node (ref "R43") (pin "2") (pinfunction "2_2") (pintype "passive"))
      (node (ref "R45") (pin "1") (pinfunction "1_1") (pintype "passive"))
      (node (ref "R47") (pin "2") (pinfunction "2_2") (pintype "passive"))
      (node (ref "R5") (pin "2") (pinfunction "2_2") (pintype "passive"))
      (node (ref "R56") (pin "1") (pinfunction "1_1") (pintype "passive"))
      (node (ref "SW1") (pin "1") (pinfunction "1_1") (pintype "bidirectional"))
      (node (ref "SW1") (pin "3") (pinfunction "3_3") (pintype "bidirectional"))
      (node (ref "SW1") (pin "4") (pinfunction "4_4") (pintype "bidirectional"))
      (node (ref "SW2") (pin "1") (pinfunction "1_1") (pintype "bidirectional"))
      (node (ref "SW2") (pin "3") (pinfunction "3_3") (pintype "bidirectional"))
      (node (ref "SW2") (pin "4") (pinfunction "4_4") (pintype "bidirectional"))
      (node (ref "U1") (pin "3") (pinfunction "GND_3") (pintype "bidirectional"))
      (node (ref "U1") (pin "EP") (pinfunction "EP_EP") (pintype "bidirectional"))
      (node (ref "U10") (pin "7") (pinfunction "GND_7") (pintype "bidirectional"))
      (node (ref "U10") (pin "9") (pinfunction "PE_9") (pintype "bidirectional"))
      (node (ref "U2") (pin "4") (pinfunction "GND_4") (pintype "bidirectional"))
      (node (ref "U3") (pin "2") (pinfunction "GND_2") (pintype "bidirectional"))
      (node (ref "U4") (pin "10") (pinfunction "10_10") (pintype "bidirectional"))
      (node (ref "U4") (pin "11") (pinfunction "11_11") (pintype "bidirectional"))
      (node (ref "U4") (pin "12") (pinfunction "11_12") (pintype "bidirectional"))
      (node (ref "U4") (pin "6") (pinfunction "VSS_6") (pintype "bidirectional"))
      (node (ref "U5") (pin "2") (pinfunction "GND_2") (pintype "bidirectional"))
      (node (ref "X1") (pin "2") (pinfunction "G2_2") (pintype "power_in"))
      (node (ref "X1") (pin "4") (pinfunction "G1_4") (pintype "power_in"))
    )
    (net (code "22") (name "I46_CAM_D9") (class "Default")
      (node (ref "FPC2") (pin "13") (pinfunction "13_13") (pintype "bidirectional"))
      (node (ref "IC2") (pin "52") (pinfunction "GPIO46_52") (pintype "bidirectional"))
    )
    (net (code "23") (name "IO0_BOOT") (class "Default")
      (node (ref "IC2") (pin "5") (pinfunction "GPIO0_5") (pintype "bidirectional"))
      (node (ref "R55") (pin "2") (pinfunction "2_2") (pintype "passive"))
      (node (ref "SW1") (pin "2") (pinfunction "2_2") (pintype "bidirectional"))
      (node (ref "U8") (pin "3") (pinfunction "C2_3") (pintype "bidirectional"))
    )
    (net (code "24") (name "IO1_MIC_CLK") (class "Default")
      (node (ref "MIC1") (pin "6") (pinfunction "CLK_6") (pintype "bidirectional"))
      (node (ref "R1") (pin "1") (pinfunction "1_1") (pintype "passive"))
    )
    (net (code "25") (name "IO2_MIC_DATA") (class "Default")
      (node (ref "MIC1") (pin "5") (pinfunction "DATA_5") (pintype "bidirectional"))
      (node (ref "R2") (pin "1") (pinfunction "1_1") (pintype "passive"))
    )
    (net (code "26") (name "IO3_SDATA") (class "Default")
      (node (ref "IC2") (pin "8") (pinfunction "GPIO3_8") (pintype "bidirectional"))
      (node (ref "R26") (pin "2") (pinfunction "2_2") (pintype "passive"))
    )
    (net (code "27") (name "IO4_LRCLK") (class "Default")
      (node (ref "IC2") (pin "9") (pinfunction "GPIO4_9") (pintype "bidirectional"))
      (node (ref "R24") (pin "2") (pinfunction "2_2") (pintype "passive"))
    )
    (net (code "28") (name "IO5_BCLK") (class "Default")
      (node (ref "IC2") (pin "10") (pinfunction "GPIO5_10") (pintype "bidirectional"))
      (node (ref "R25") (pin "2") (pinfunction "2_2") (pintype "passive"))
    )
    (net (code "29") (name "IO6_SD_MISO") (class "Default")
      (node (ref "IC2") (pin "11") (pinfunction "GPIO6_11") (pintype "bidirectional"))
      (node (ref "R33") (pin "1") (pinfunction "1_1") (pintype "passive"))
      (node (ref "U4") (pin "7") (pinfunction "DAT0_7") (pintype "bidirectional"))
    )
    (net (code "30") (name "IO7_SD_CLK") (class "Default")
      (node (ref "IC2") (pin "12") (pinfunction "GPIO7_12") (pintype "bidirectional"))
      (node (ref "U4") (pin "5") (pinfunction "CLK_5") (pintype "bidirectional"))
    )
    (net (code "31") (name "IO8_SD_MOSI") (class "Default")
      (node (ref "IC2") (pin "13") (pinfunction "GPIO8_13") (pintype "bidirectional"))
      (node (ref "R32") (pin "1") (pinfunction "1_1") (pintype "passive"))
      (node (ref "U4") (pin "3") (pinfunction "CMD_3") (pintype "bidirectional"))
    )
    (net (code "32") (name "IO9_LCD_D{slash}C") (class "Default")
      (node (ref "FPC1") (pin "7") (pinfunction "7_7") (pintype "bidirectional"))
      (node (ref "IC2") (pin "14") (pinfunction "GPIO9_14") (pintype "bidirectional"))
    )
    (net (code "33") (name "IO10_LCD_CS") (class "Default")
      (node (ref "FPC1") (pin "8") (pinfunction "8_8") (pintype "bidirectional"))
      (node (ref "IC2") (pin "15") (pinfunction "GPIO10_15") (pintype "bidirectional"))
    )
    (net (code "34") (name "IO11_TP_INT") (class "Default")
      (node (ref "FPC1") (pin "16") (pinfunction "16_16") (pintype "bidirectional"))
      (node (ref "IC2") (pin "16") (pinfunction "GPIO11_16") (pintype "bidirectional"))
    )
    (net (code "35") (name "IO12_TP_TRST") (class "Default")
      (node (ref "FPC1") (pin "15") (pinfunction "15_15") (pintype "bidirectional"))
      (node (ref "IC2") (pin "17") (pinfunction "GPIO12_17") (pintype "bidirectional"))
    )
    (net (code "36") (name "IO13_LCD_MOSI") (class "Default")
      (node (ref "FPC1") (pin "10") (pinfunction "10_10") (pintype "bidirectional"))
      (node (ref "IC2") (pin "18") (pinfunction "GPIO13_18") (pintype "bidirectional"))
    )
    (net (code "37") (name "IO14_LCD_SCK") (class "Default")
      (node (ref "FPC1") (pin "9") (pinfunction "9_9") (pintype "bidirectional"))
      (node (ref "IC2") (pin "19") (pinfunction "GPIO14_19") (pintype "bidirectional"))
    )
    (net (code "38") (name "IO15_SCL") (class "Default")
      (node (ref "FPC1") (pin "13") (pinfunction "13_13") (pintype "bidirectional"))
      (node (ref "IC10") (pin "19") (pinfunction "SCL_19") (pintype "bidirectional"))
      (node (ref "IC2") (pin "21") (pinfunction "XTAL_32K_P_21") (pintype "bidirectional"))
      (node (ref "P4") (pin "P$1") (pinfunction "P$1_P$1") (pintype "bidirectional"))
      (node (ref "R40") (pin "2") (pinfunction "2_2") (pintype "passive"))
    )
    (net (code "39") (name "IO16_SDA") (class "Default")
      (node (ref "FPC1") (pin "14") (pinfunction "14_14") (pintype "bidirectional"))
      (node (ref "IC10") (pin "20") (pinfunction "SDA_20") (pintype "bidirectional"))
      (node (ref "IC2") (pin "22") (pinfunction "XTAL_32K_N_22") (pintype "bidirectional"))
      (node (ref "P3") (pin "P$1") (pinfunction "P$1_P$1") (pintype "bidirectional"))
      (node (ref "R39") (pin "2") (pinfunction "2_2") (pintype "passive"))
    )
    (net (code "40") (name "IO17_CAM_D4") (class "Default")
      (node (ref "FPC2") (pin "3") (pinfunction "3_3") (pintype "bidirectional"))
      (node (ref "IC2") (pin "23") (pinfunction "GPIO17_23") (pintype "bidirectional"))
    )
    (net (code "41") (name "IO18_CAM_D3") (class "Default")
      (node (ref "FPC2") (pin "4") (pinfunction "4_4") (pintype "bidirectional"))
      (node (ref "IC2") (pin "24") (pinfunction "GPIO18_24") (pintype "bidirectional"))
    )
    (net (code "42") (name "IO19_CAM_D5") (class "Default")
      (node (ref "FPC2") (pin "5") (pinfunction "5_5") (pintype "bidirectional"))
      (node (ref "IC2") (pin "25") (pinfunction "GPIO19_25") (pintype "bidirectional"))
    )
    (net (code "43") (name "IO20_CAM_D2") (class "Default")
      (node (ref "FPC2") (pin "6") (pinfunction "6_6") (pintype "bidirectional"))
      (node (ref "IC2") (pin "26") (pinfunction "GPIO20_26") (pintype "bidirectional"))
    )
    (net (code "44") (name "IO21_CAM_D6") (class "Default")
      (node (ref "FPC2") (pin "7") (pinfunction "7_7") (pintype "bidirectional"))
      (node (ref "IC2") (pin "27") (pinfunction "GPIO21_27") (pintype "bidirectional"))
    )
    (net (code "45") (name "IO38_CAM_D8") (class "Default")
      (node (ref "FPC2") (pin "11") (pinfunction "11_11") (pintype "bidirectional"))
      (node (ref "IC2") (pin "43") (pinfunction "GPIO38_43") (pintype "bidirectional"))
    )
    (net (code "46") (name "IO39_CAM-MCLK") (class "Default")
      (node (ref "FPC2") (pin "12") (pinfunction "12_12") (pintype "bidirectional"))
      (node (ref "IC2") (pin "44") (pinfunction "MTCK_44") (pintype "bidirectional"))
    )
    (net (code "47") (name "IO40_CAM_SCL") (class "Default")
      (node (ref "FPC2") (pin "20") (pinfunction "20_20") (pintype "bidirectional"))
      (node (ref "IC2") (pin "45") (pinfunction "MTDO_45") (pintype "bidirectional"))
    )
    (net (code "48") (name "IO41_CAM_SDA") (class "Default")
      (node (ref "FPC2") (pin "22") (pinfunction "22_22") (pintype "bidirectional"))
      (node (ref "IC2") (pin "47") (pinfunction "MTDI_47") (pintype "bidirectional"))
    )
    (net (code "49") (name "IO42_CAM_VS") (class "Default")
      (node (ref "FPC2") (pin "18") (pinfunction "18_18") (pintype "bidirectional"))
      (node (ref "IC2") (pin "48") (pinfunction "MTMS_48") (pintype "bidirectional"))
    )
    (net (code "50") (name "IO45_CAM_HS") (class "Default")
      (node (ref "FPC2") (pin "16") (pinfunction "16_16") (pintype "bidirectional"))
      (node (ref "IC2") (pin "51") (pinfunction "GPIO45_51") (pintype "bidirectional"))
    )
    (net (code "51") (name "IO47_CAM_D7") (class "Default")
      (node (ref "FPC2") (pin "9") (pinfunction "9_9") (pintype "bidirectional"))
      (node (ref "IC2") (pin "37") (pinfunction "SPICLK_P_37") (pintype "bidirectional"))
    )
    (net (code "52") (name "IO48_CAM_PCLK") (class "Default")
      (node (ref "FPC2") (pin "8") (pinfunction "8_8") (pintype "bidirectional"))
      (node (ref "IC2") (pin "36") (pinfunction "SPICLK_N_36") (pintype "bidirectional"))
    )
    (net (code "53") (name "LCD_RESET") (class "Default")
      (node (ref "C26") (pin "2") (pinfunction "2_2") (pintype "passive"))
      (node (ref "D12") (pin "+") (pinfunction "+_+") (pintype "passive"))
      (node (ref "FPC1") (pin "11") (pinfunction "11_11") (pintype "bidirectional"))
      (node (ref "R38") (pin "1") (pinfunction "1_1") (pintype "passive"))
    )
    (net (code "54") (name "LEDK") (class "Default")
      (node (ref "FPC1") (pin "2") (pinfunction "2_2") (pintype "bidirectional"))
      (node (ref "R37") (pin "2") (pinfunction "2_2") (pintype "passive"))
    )
    (net (code "55") (name "NS_3V3") (class "Default")
      (node (ref "Q8") (pin "3") (pinfunction "D_3") (pintype "passive"))
      (node (ref "R23") (pin "2") (pinfunction "2_2") (pintype "passive"))
    )
    (net (code "56") (name "Net-(ANT1-FEED)") (class "Default")
      (node (ref "ANT1") (pin "1") (pinfunction "FEED_1") (pintype "passive"))
      (node (ref "C3") (pin "1") (pinfunction "1_1") (pintype "passive"))
      (node (ref "L1") (pin "1") (pinfunction "1_1") (pintype "passive"))
    )
    (net (code "57") (name "Net-(C29-Pad1)") (class "Default")
      (node (ref "C29") (pin "1") (pinfunction "1_1") (pintype "passive"))
      (node (ref "FPC2") (pin "14") (pinfunction "14_14") (pintype "bidirectional"))
      (node (ref "R16") (pin "1") (pinfunction "1_1") (pintype "passive"))
      (node (ref "R54") (pin "1") (pinfunction "1_1") (pintype "passive"))
    )
    (net (code "58") (name "Net-(D2-Pad3)") (class "Default")
      (node (ref "D2") (pin "3") (pinfunction "3_3") (pintype "passive"))
      (node (ref "R44") (pin "2") (pinfunction "2_2") (pintype "passive"))
    )
    (net (code "59") (name "Net-(D2-Pad4)") (class "Default")
      (node (ref "D2") (pin "4") (pinfunction "4_4") (pintype "passive"))
      (node (ref "R52") (pin "2") (pinfunction "2_2") (pintype "passive"))
    )
    (net (code "60") (name "Net-(D6-Pad-)") (class "Default")
      (node (ref "D6") (pin "-") (pinfunction "-_-") (pintype "passive"))
      (node (ref "R43") (pin "1") (pinfunction "1_1") (pintype "passive"))
    )
    (net (code "61") (name "Net-(FPC2-Pad17)") (class "Default")
      (node (ref "FPC2") (pin "17") (pinfunction "17_17") (pintype "bidirectional"))
      (node (ref "R41") (pin "1") (pinfunction "1_1") (pintype "passive"))
    )
    (net (code "62") (name "Net-(IC2-GPIO1)") (class "Default")
      (node (ref "IC2") (pin "6") (pinfunction "GPIO1_6") (pintype "bidirectional"))
      (node (ref "R1") (pin "2") (pinfunction "2_2") (pintype "passive"))
    )
    (net (code "63") (name "Net-(IC2-GPIO2)") (class "Default")
      (node (ref "IC2") (pin "7") (pinfunction "GPIO2_7") (pintype "bidirectional"))
      (node (ref "R2") (pin "2") (pinfunction "2_2") (pintype "passive"))
    )
    (net (code "64") (name "Net-(IC2-LNA_IN)") (class "Default")
      (node (ref "C4") (pin "1") (pinfunction "1_1") (pintype "passive"))
      (node (ref "IC2") (pin "1") (pinfunction "LNA_IN_1") (pintype "bidirectional"))
      (node (ref "L1") (pin "2") (pinfunction "2_2") (pintype "passive"))
    )
    (net (code "65") (name "Net-(IC2-XTAL_N)") (class "Default")
      (node (ref "C2") (pin "2") (pinfunction "2_2") (pintype "passive"))
      (node (ref "IC2") (pin "53") (pinfunction "XTAL_N_53") (pintype "bidirectional"))
      (node (ref "X1") (pin "3") (pinfunction "X2_3") (pintype "bidirectional"))
    )
    (net (code "66") (name "Net-(IC2-XTAL_P)") (class "Default")
      (node (ref "C1") (pin "2") (pinfunction "2_2") (pintype "passive"))
      (node (ref "IC2") (pin "54") (pinfunction "XTAL_P_54") (pintype "bidirectional"))
      (node (ref "X1") (pin "1") (pinfunction "X1_1") (pintype "bidirectional"))
    )
    (net (code "67") (name "Net-(LED2-B)") (class "Default")
      (node (ref "LED2") (pin "4") (pinfunction "B_4") (pintype "bidirectional"))
      (node (ref "R50") (pin "2") (pinfunction "2_2") (pintype "passive"))
    )
    (net (code "68") (name "Net-(LED2-G)") (class "Default")
      (node (ref "LED2") (pin "1") (pinfunction "G_1") (pintype "bidirectional"))
      (node (ref "R49") (pin "2") (pinfunction "2_2") (pintype "passive"))
    )
    (net (code "69") (name "Net-(LED2-R)") (class "Default")
      (node (ref "LED2") (pin "2") (pinfunction "R_2") (pintype "bidirectional"))
      (node (ref "R48") (pin "2") (pinfunction "2_2") (pintype "passive"))
    )
    (net (code "70") (name "Net-(LED3-Pad2)") (class "Default")
      (node (ref "LED3") (pin "2") (pinfunction "2_2") (pintype "bidirectional"))
      (node (ref "R27") (pin "2") (pinfunction "2_2") (pintype "passive"))
    )
    (net (code "71") (name "Net-(MIC1-L{slash}R)") (class "Default")
      (node (ref "MIC1") (pin "2") (pinfunction "L/R_2") (pintype "bidirectional"))
      (node (ref "R3") (pin "1") (pinfunction "1_1") (pintype "passive"))
    )
    (net (code "72") (name "Net-(MIC1-VDD)") (class "Default")
      (node (ref "C20") (pin "1") (pinfunction "1_1") (pintype "passive"))
      (node (ref "FB4") (pin "1") (pinfunction "1_1") (pintype "passive"))
      (node (ref "MIC1") (pin "4") (pinfunction "VDD_4") (pintype "bidirectional"))
    )
    (net (code "73") (name "Net-(Q4-G)") (class "Default")
      (node (ref "Q4") (pin "1") (pinfunction "G_1") (pintype "passive"))
      (node (ref "Q5") (pin "3") (pinfunction "C_3") (pintype "passive"))
      (node (ref "R21") (pin "1") (pinfunction "1_1") (pintype "passive"))
    )
    (net (code "74") (name "Net-(Q5-B)") (class "Default")
      (node (ref "Q5") (pin "1") (pinfunction "B_1") (pintype "passive"))
      (node (ref "R22") (pin "1") (pinfunction "1_1") (pintype "passive"))
      (node (ref "R42") (pin "2") (pinfunction "2_2") (pintype "passive"))
    )
    (net (code "75") (name "Net-(Q7-B)") (class "Default")
      (node (ref "Q7") (pin "1") (pinfunction "B_1") (pintype "passive"))
      (node (ref "R28") (pin "1") (pinfunction "1_1") (pintype "passive"))
      (node (ref "R29") (pin "2") (pinfunction "2_2") (pintype "passive"))
    )
    (net (code "76") (name "Net-(Q7-C)") (class "Default")
      (node (ref "Q7") (pin "3") (pinfunction "C_3") (pintype "passive"))
      (node (ref "R27") (pin "1") (pinfunction "1_1") (pintype "passive"))
    )
    (net (code "77") (name "Net-(U1-RXD)") (class "Default")
      (node (ref "R8") (pin "2") (pinfunction "2_2") (pintype "passive"))
      (node (ref "U1") (pin "9") (pinfunction "RXD_9") (pintype "bidirectional"))
    )
    (net (code "78") (name "Net-(U1-TXD)") (class "Default")
      (node (ref "R9") (pin "2") (pinfunction "2_2") (pintype "passive"))
      (node (ref "U1") (pin "8") (pinfunction "TXD_8") (pintype "bidirectional"))
    )
    (net (code "79") (name "Net-(U1-UD+)") (class "Default")
      (node (ref "R6") (pin "1") (pinfunction "1_1") (pintype "passive"))
      (node (ref "U1") (pin "1") (pinfunction "UD+_1") (pintype "bidirectional"))
    )
    (net (code "80") (name "Net-(U1-UD-)") (class "Default")
      (node (ref "R7") (pin "1") (pinfunction "1_1") (pintype "passive"))
      (node (ref "U1") (pin "2") (pinfunction "UD-_2") (pintype "bidirectional"))
    )
    (net (code "81") (name "Net-(U1-V3)") (class "Default")
      (node (ref "C6") (pin "1") (pinfunction "1_1") (pintype "passive"))
      (node (ref "U1") (pin "10") (pinfunction "V3_10") (pintype "bidirectional"))
    )
    (net (code "82") (name "Net-(U3-FB)") (class "Default")
      (node (ref "R19") (pin "2") (pinfunction "2_2") (pintype "passive"))
      (node (ref "R20") (pin "1") (pinfunction "1_1") (pintype "passive"))
      (node (ref "U3") (pin "5") (pinfunction "FB_5") (pintype "bidirectional"))
    )
    (net (code "83") (name "Net-(U3-SW)") (class "Default")
      (node (ref "L2") (pin "1") (pinfunction "1_1") (pintype "bidirectional"))
      (node (ref "U3") (pin "3") (pinfunction "SW_3") (pintype "bidirectional"))
    )
    (net (code "84") (name "Net-(U4-CD{slash}DAT3)") (class "Default")
      (node (ref "R31") (pin "1") (pinfunction "1_1") (pintype "passive"))
      (node (ref "U4") (pin "2") (pinfunction "CD/DAT3_2") (pintype "bidirectional"))
    )
    (net (code "85") (name "Net-(U4-DAT1)") (class "Default")
      (node (ref "R34") (pin "1") (pinfunction "1_1") (pintype "passive"))
      (node (ref "U4") (pin "8") (pinfunction "DAT1_8") (pintype "bidirectional"))
    )
    (net (code "86") (name "Net-(U4-DAT2)") (class "Default")
      (node (ref "R30") (pin "1") (pinfunction "1_1") (pintype "passive"))
      (node (ref "U4") (pin "1") (pinfunction "DAT2_1") (pintype "bidirectional"))
    )
    (net (code "87") (name "Net-(U5-CHG)") (class "Default")
      (node (ref "R52") (pin "1") (pinfunction "1_1") (pintype "passive"))
      (node (ref "U5") (pin "1") (pinfunction "CHG_1") (pintype "bidirectional"))
    )
    (net (code "88") (name "Net-(U5-PRO)") (class "Default")
      (node (ref "R45") (pin "2") (pinfunction "2_2") (pintype "passive"))
      (node (ref "U5") (pin "6") (pinfunction "PRO_6") (pintype "bidirectional"))
    )
    (net (code "89") (name "Net-(U5-STD)") (class "Default")
      (node (ref "R44") (pin "1") (pinfunction "1_1") (pintype "passive"))
      (node (ref "U5") (pin "5") (pinfunction "STD_5") (pintype "bidirectional"))
    )
    (net (code "90") (name "Net-(U8-B1)") (class "Default")
      (node (ref "R10") (pin "1") (pinfunction "1_1") (pintype "passive"))
      (node (ref "U8") (pin "2") (pinfunction "B1_2") (pintype "input"))
    )
    (net (code "91") (name "Net-(U8-B2)") (class "Default")
      (node (ref "R11") (pin "1") (pinfunction "1_1") (pintype "passive"))
      (node (ref "U8") (pin "5") (pinfunction "B2_5") (pintype "input"))
    )
    (net (code "92") (name "Net-(U10-BCLK)") (class "Default")
      (node (ref "R25") (pin "1") (pinfunction "1_1") (pintype "passive"))
      (node (ref "U10") (pin "3") (pinfunction "BCLK_3") (pintype "bidirectional"))
    )
    (net (code "93") (name "Net-(U10-CTRL)") (class "Default")
      (node (ref "R23") (pin "1") (pinfunction "1_1") (pintype "passive"))
      (node (ref "R56") (pin "2") (pinfunction "2_2") (pintype "passive"))
      (node (ref "U10") (pin "1") (pinfunction "CTRL_1") (pintype "bidirectional"))
    )
    (net (code "94") (name "Net-(U10-LRCLK)") (class "Default")
      (node (ref "R24") (pin "1") (pinfunction "1_1") (pintype "passive"))
      (node (ref "U10") (pin "2") (pinfunction "LRCLK_2") (pintype "bidirectional"))
    )
    (net (code "95") (name "Net-(U10-SDATA)") (class "Default")
      (node (ref "R26") (pin "1") (pinfunction "1_1") (pintype "passive"))
      (node (ref "U10") (pin "4") (pinfunction "SDATA_4") (pintype "bidirectional"))
    )
    (net (code "96") (name "Net-(U10-VON)") (class "Default")
      (node (ref "FB3") (pin "1") (pinfunction "1_1") (pintype "passive"))
      (node (ref "U10") (pin "5") (pinfunction "VON_5") (pintype "bidirectional"))
    )
    (net (code "97") (name "Net-(U10-VOP)") (class "Default")
      (node (ref "FB2") (pin "1") (pinfunction "1_1") (pintype "passive"))
      (node (ref "U10") (pin "8") (pinfunction "VOP_8") (pintype "bidirectional"))
    )
    (net (code "98") (name "RTS") (class "Default")
      (node (ref "R11") (pin "2") (pinfunction "2_2") (pintype "passive"))
      (node (ref "U1") (pin "6") (pinfunction "RTS#_6") (pintype "bidirectional"))
      (node (ref "U8") (pin "1") (pinfunction "E1_1") (pintype "bidirectional"))
    )
    (net (code "99") (name "RXD0_H") (class "Default")
      (node (ref "D14") (pin "2") (pinfunction "2_2") (pintype "bidirectional"))
      (node (ref "J5") (pin "3") (pinfunction "3_3") (pintype "bidirectional"))
      (node (ref "Q2") (pin "3") (pinfunction "D_3") (pintype "passive"))
      (node (ref "R13") (pin "2") (pinfunction "2_2") (pintype "passive"))
      (node (ref "R9") (pin "1") (pinfunction "1_1") (pintype "passive"))
    )
    (net (code "100") (name "SPICLK") (class "Default")
      (node (ref "IC2") (pin "33") (pinfunction "SPICLK_33") (pintype "bidirectional"))
      (node (ref "U2") (pin "6") (pinfunction "CLK_6") (pintype "bidirectional"))
    )
    (net (code "101") (name "SPICS0") (class "Default")
      (node (ref "IC2") (pin "32") (pinfunction "SPICS0_32") (pintype "bidirectional"))
      (node (ref "U2") (pin "1") (pinfunction "/CS_1") (pintype "bidirectional"))
    )
    (net (code "102") (name "SPID") (class "Default")
      (node (ref "IC2") (pin "35") (pinfunction "SPID_35") (pintype "bidirectional"))
      (node (ref "U2") (pin "5") (pinfunction "DI(IO0)_5") (pintype "bidirectional"))
    )
    (net (code "103") (name "SPIHD") (class "Default")
      (node (ref "IC2") (pin "30") (pinfunction "SPIHD_30") (pintype "bidirectional"))
      (node (ref "U2") (pin "7") (pinfunction "/HOLD(IO3)_7") (pintype "bidirectional"))
    )
    (net (code "104") (name "SPIQ") (class "Default")
      (node (ref "IC2") (pin "34") (pinfunction "SPIQ_34") (pintype "bidirectional"))
      (node (ref "U2") (pin "2") (pinfunction "DO(IO1)_2") (pintype "bidirectional"))
    )
    (net (code "105") (name "SPIWP") (class "Default")
      (node (ref "IC2") (pin "31") (pinfunction "SPIWP_31") (pintype "bidirectional"))
      (node (ref "U2") (pin "3") (pinfunction "/WP(IO2)_3") (pintype "bidirectional"))
    )
    (net (code "106") (name "TXD0_H") (class "Default")
      (node (ref "D15") (pin "2") (pinfunction "2_2") (pintype "bidirectional"))
      (node (ref "J5") (pin "4") (pinfunction "4_4") (pintype "bidirectional"))
      (node (ref "Q1") (pin "3") (pinfunction "D_3") (pintype "passive"))
      (node (ref "R12") (pin "2") (pinfunction "2_2") (pintype "passive"))
      (node (ref "R8") (pin "1") (pinfunction "1_1") (pintype "passive"))
    )
    (net (code "107") (name "USB_D+") (class "Default")
      (node (ref "D9") (pin "2") (pinfunction "2_2") (pintype "bidirectional"))
      (node (ref "J1") (pin "A6") (pinfunction "A6_A6") (pintype "bidirectional"))
      (node (ref "J1") (pin "B6") (pinfunction "B6_B6") (pintype "bidirectional"))
      (node (ref "R6") (pin "2") (pinfunction "2_2") (pintype "passive"))
    )
    (net (code "108") (name "USB_D-") (class "Default")
      (node (ref "D10") (pin "2") (pinfunction "2_2") (pintype "bidirectional"))
      (node (ref "J1") (pin "A7") (pinfunction "A7_A7") (pintype "bidirectional"))
      (node (ref "J1") (pin "B7") (pinfunction "B7_B7") (pintype "bidirectional"))
      (node (ref "R7") (pin "2") (pinfunction "2_2") (pintype "passive"))
    )
    (net (code "109") (name "VBAT") (class "Default")
      (node (ref "C17") (pin "2") (pinfunction "2_2") (pintype "passive"))
      (node (ref "J3") (pin "2") (pinfunction "2_2") (pintype "bidirectional"))
      (node (ref "Q3") (pin "3") (pinfunction "D_3") (pintype "passive"))
      (node (ref "R53") (pin "1") (pinfunction "1_1") (pintype "passive"))
      (node (ref "U5") (pin "3") (pinfunction "BAT_3") (pintype "bidirectional"))
    )
    (net (code "110") (name "VBUS1") (class "Default")
      (node (ref "C5") (pin "1") (pinfunction "1_1") (pintype "passive"))
      (node (ref "D1") (pin "+") (pinfunction "+_+") (pintype "passive"))
      (node (ref "D3") (pin "+") (pinfunction "+_+") (pintype "passive"))
      (node (ref "D4") (pin "2") (pinfunction "2_2") (pintype "bidirectional"))
      (node (ref "J1") (pin "A4") (pinfunction "A4_A4") (pintype "bidirectional"))
      (node (ref "J1") (pin "A9") (pinfunction "A9_A9") (pintype "bidirectional"))
      (node (ref "J1") (pin "B4") (pinfunction "B4_B4") (pintype "bidirectional"))
      (node (ref "J1") (pin "B9") (pinfunction "B9_B9") (pintype "bidirectional"))
      (node (ref "U1") (pin "7") (pinfunction "VCC_7") (pintype "bidirectional"))
    )
    (net (code "111") (name "VBUS2") (class "Default")
      (node (ref "D5") (pin "2") (pinfunction "2_2") (pintype "bidirectional"))
      (node (ref "D8") (pin "+") (pinfunction "+_+") (pintype "passive"))
      (node (ref "J5") (pin "2") (pinfunction "2_2") (pintype "bidirectional"))
      (node (ref "L3") (pin "+") (pinfunction "+_+") (pintype "passive"))
    )
    (net (code "112") (name "VDD_SPI") (class "Default")
      (node (ref "C37") (pin "2") (pinfunction "2_2") (pintype "passive"))
      (node (ref "IC2") (pin "29") (pinfunction "VDD_SPI_29") (pintype "bidirectional"))
      (node (ref "U2") (pin "8") (pinfunction "VCC_8") (pintype "bidirectional"))
    )
    (net (code "113") (name "VIN") (class "Default")
      (node (ref "C11") (pin "2") (pinfunction "2_2") (pintype "passive"))
      (node (ref "C12") (pin "1") (pinfunction "1_1") (pintype "passive"))
      (node (ref "D1") (pin "-") (pinfunction "-_-") (pintype "passive"))
      (node (ref "L3") (pin "-") (pinfunction "-_-") (pintype "passive"))
      (node (ref "Q3") (pin "2") (pinfunction "S_2") (pintype "passive"))
      (node (ref "R12") (pin "1") (pinfunction "1_1") (pintype "passive"))
      (node (ref "R13") (pin "1") (pinfunction "1_1") (pintype "passive"))
      (node (ref "U3") (pin "1") (pinfunction "EN_1") (pintype "bidirectional"))
      (node (ref "U3") (pin "4") (pinfunction "VIN_4") (pintype "bidirectional"))
    )
    (net (code "114") (name "VIN_C") (class "Default")
      (node (ref "C38") (pin "2") (pinfunction "2_2") (pintype "passive"))
      (node (ref "D3") (pin "-") (pinfunction "-_-") (pintype "passive"))
      (node (ref "D8") (pin "-") (pinfunction "-_-") (pintype "passive"))
      (node (ref "Q3") (pin "1") (pinfunction "G_1") (pintype "passive"))
      (node (ref "R18") (pin "1") (pinfunction "1_1") (pintype "passive"))
      (node (ref "R53") (pin "2") (pinfunction "2_2") (pintype "passive"))
      (node (ref "U5") (pin "4") (pinfunction "VCC_4") (pintype "bidirectional"))
    )
    (net (code "115") (name "VON") (class "Default")
      (node (ref "C18") (pin "2") (pinfunction "2_2") (pintype "passive"))
      (node (ref "FB3") (pin "2") (pinfunction "2_2") (pintype "passive"))
      (node (ref "J4") (pin "2") (pinfunction "2_2") (pintype "bidirectional"))
    )
    (net (code "116") (name "VOP") (class "Default")
      (node (ref "C19") (pin "1") (pinfunction "1_1") (pintype "passive"))
      (node (ref "FB2") (pin "2") (pinfunction "2_2") (pintype "passive"))
      (node (ref "J4") (pin "1") (pinfunction "1_1") (pintype "bidirectional"))
    )
    (net (code "117") (name "unconnected-(FPC2-Pad1)") (class "Default")
      (node (ref "FPC2") (pin "1") (pinfunction "1_1") (pintype "bidirectional"))
    )
    (net (code "118") (name "unconnected-(FPC2-Pad2)") (class "Default")
      (node (ref "FPC2") (pin "2") (pinfunction "2_2") (pintype "bidirectional"))
    )
    (net (code "119") (name "unconnected-(FPC2-Pad24)") (class "Default")
      (node (ref "FPC2") (pin "24") (pinfunction "24_24") (pintype "bidirectional"))
    )
    (net (code "120") (name "unconnected-(IC2-GPIO33-Pad38)") (class "Default")
      (node (ref "IC2") (pin "38") (pinfunction "GPIO33_38") (pintype "bidirectional"))
    )
    (net (code "121") (name "unconnected-(IC2-GPIO34-Pad39)") (class "Default")
      (node (ref "IC2") (pin "39") (pinfunction "GPIO34_39") (pintype "bidirectional"))
    )
    (net (code "122") (name "unconnected-(IC2-GPIO35-Pad40)") (class "Default")
      (node (ref "IC2") (pin "40") (pinfunction "GPIO35_40") (pintype "bidirectional"))
    )
    (net (code "123") (name "unconnected-(IC2-GPIO36-Pad41)") (class "Default")
      (node (ref "IC2") (pin "41") (pinfunction "GPIO36_41") (pintype "bidirectional"))
    )
    (net (code "124") (name "unconnected-(IC2-GPIO37-Pad42)") (class "Default")
      (node (ref "IC2") (pin "42") (pinfunction "GPIO37_42") (pintype "bidirectional"))
    )
    (net (code "125") (name "unconnected-(IC2-SPICS1-Pad28)") (class "Default")
      (node (ref "IC2") (pin "28") (pinfunction "SPICS1_28") (pintype "bidirectional"))
    )
    (net (code "126") (name "unconnected-(IC10-P0_0-Pad5)") (class "Default")
      (node (ref "IC10") (pin "5") (pinfunction "P0_0_5") (pintype "bidirectional"))
    )
    (net (code "127") (name "unconnected-(IC10-P0_1-Pad6)") (class "Default")
      (node (ref "IC10") (pin "6") (pinfunction "P0_1_6") (pintype "bidirectional"))
    )
    (net (code "128") (name "unconnected-(IC10-P0_2-Pad7)") (class "Default")
      (node (ref "IC10") (pin "7") (pinfunction "P0_2_7") (pintype "bidirectional"))
    )
    (net (code "129") (name "unconnected-(IC10-P0_3-Pad8)") (class "Default")
      (node (ref "IC10") (pin "8") (pinfunction "P0_3_8") (pintype "bidirectional"))
    )
    (net (code "130") (name "unconnected-(IC10-P0_7-Pad13)") (class "Default")
      (node (ref "IC10") (pin "13") (pinfunction "P0_7_13") (pintype "bidirectional"))
    )
    (net (code "131") (name "unconnected-(IC10-P1_2-Pad3)") (class "Default")
      (node (ref "IC10") (pin "3") (pinfunction "P1_2_3") (pintype "bidirectional"))
    )
    (net (code "132") (name "unconnected-(IC10-P1_5-Pad15)") (class "Default")
      (node (ref "IC10") (pin "15") (pinfunction "P1_5_15") (pintype "bidirectional"))
    )
    (net (code "133") (name "unconnected-(IC10-P1_6-Pad16)") (class "Default")
      (node (ref "IC10") (pin "16") (pinfunction "P1_6_16") (pintype "bidirectional"))
    )
    (net (code "134") (name "unconnected-(IC10-P1_7-Pad17)") (class "Default")
      (node (ref "IC10") (pin "17") (pinfunction "P1_7_17") (pintype "bidirectional"))
    )
    (net (code "135") (name "unconnected-(J1-PadA8)") (class "Default")
      (node (ref "J1") (pin "A8") (pinfunction "A8_A8") (pintype "bidirectional"))
    )
    (net (code "136") (name "unconnected-(J1-PadB8)") (class "Default")
      (node (ref "J1") (pin "B8") (pinfunction "B8_B8") (pintype "bidirectional"))
    )
    (net (code "137") (name "unconnected-(U1-CTS#-Pad5)") (class "Default")
      (node (ref "U1") (pin "5") (pinfunction "CTS#_5") (pintype "bidirectional"))
    )
    (net (code "138") (name "unconnected-(U4-SWITCH-Pad9)") (class "Default")
      (node (ref "U4") (pin "9") (pinfunction "SWITCH_9") (pintype "bidirectional"))
    )
  )
)
